# Sheet_1_2024-03-04.net
KiCad netlist of a schematic drawn in Altium Designer
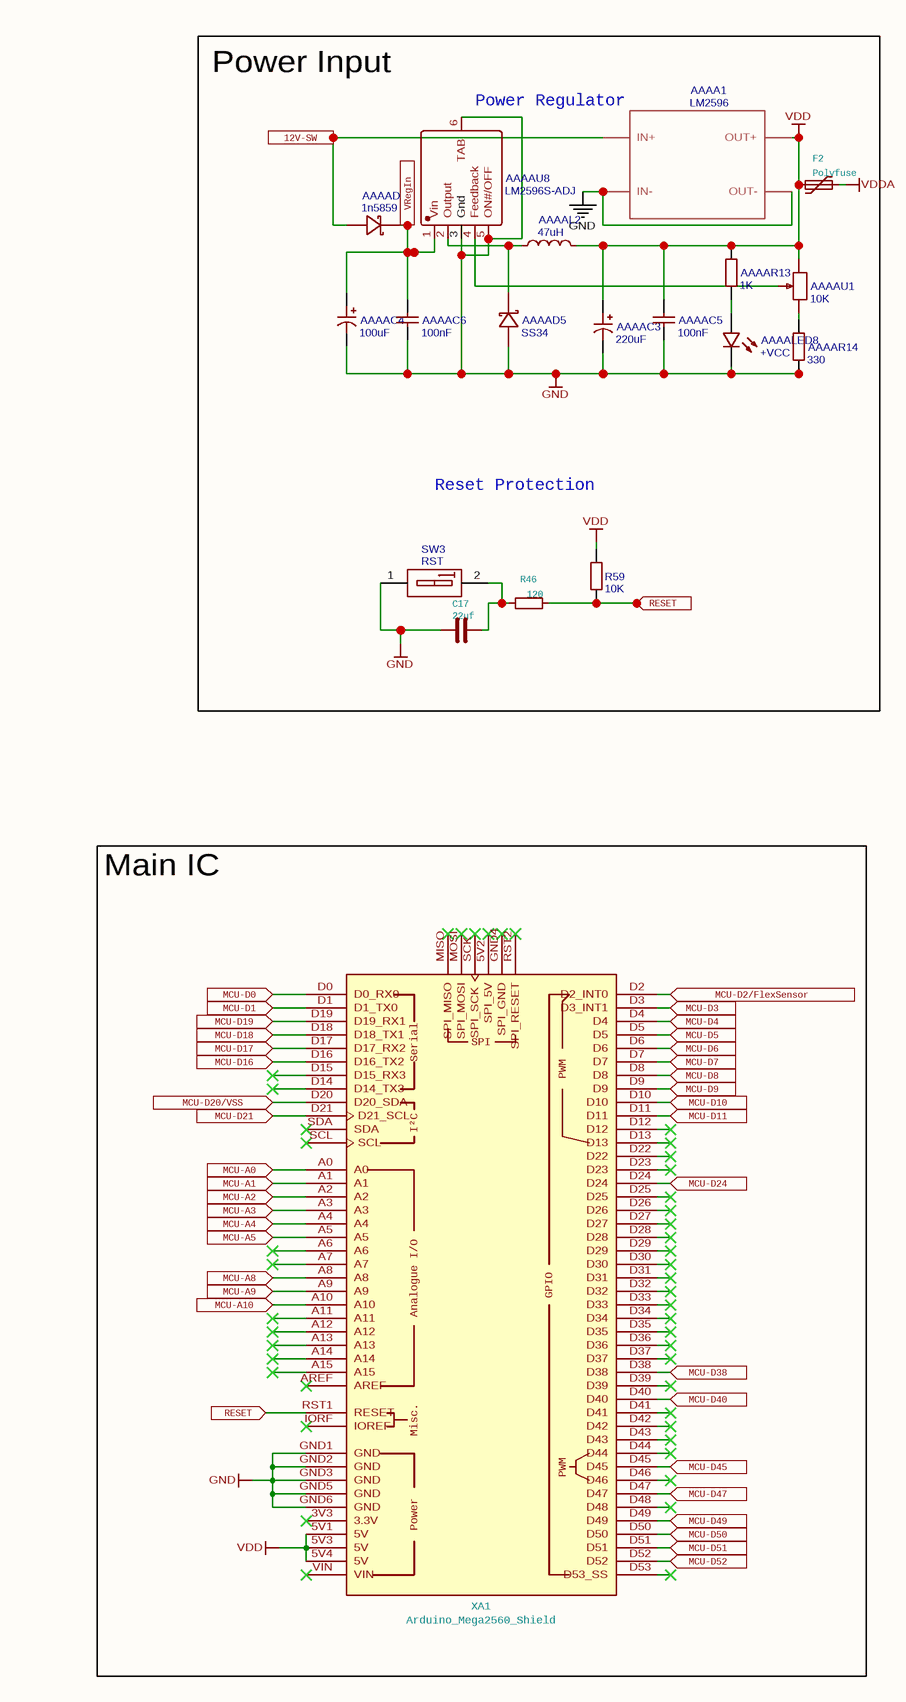
[diagram p0: Sheet_1_2024-03-04.schdoc, top left]
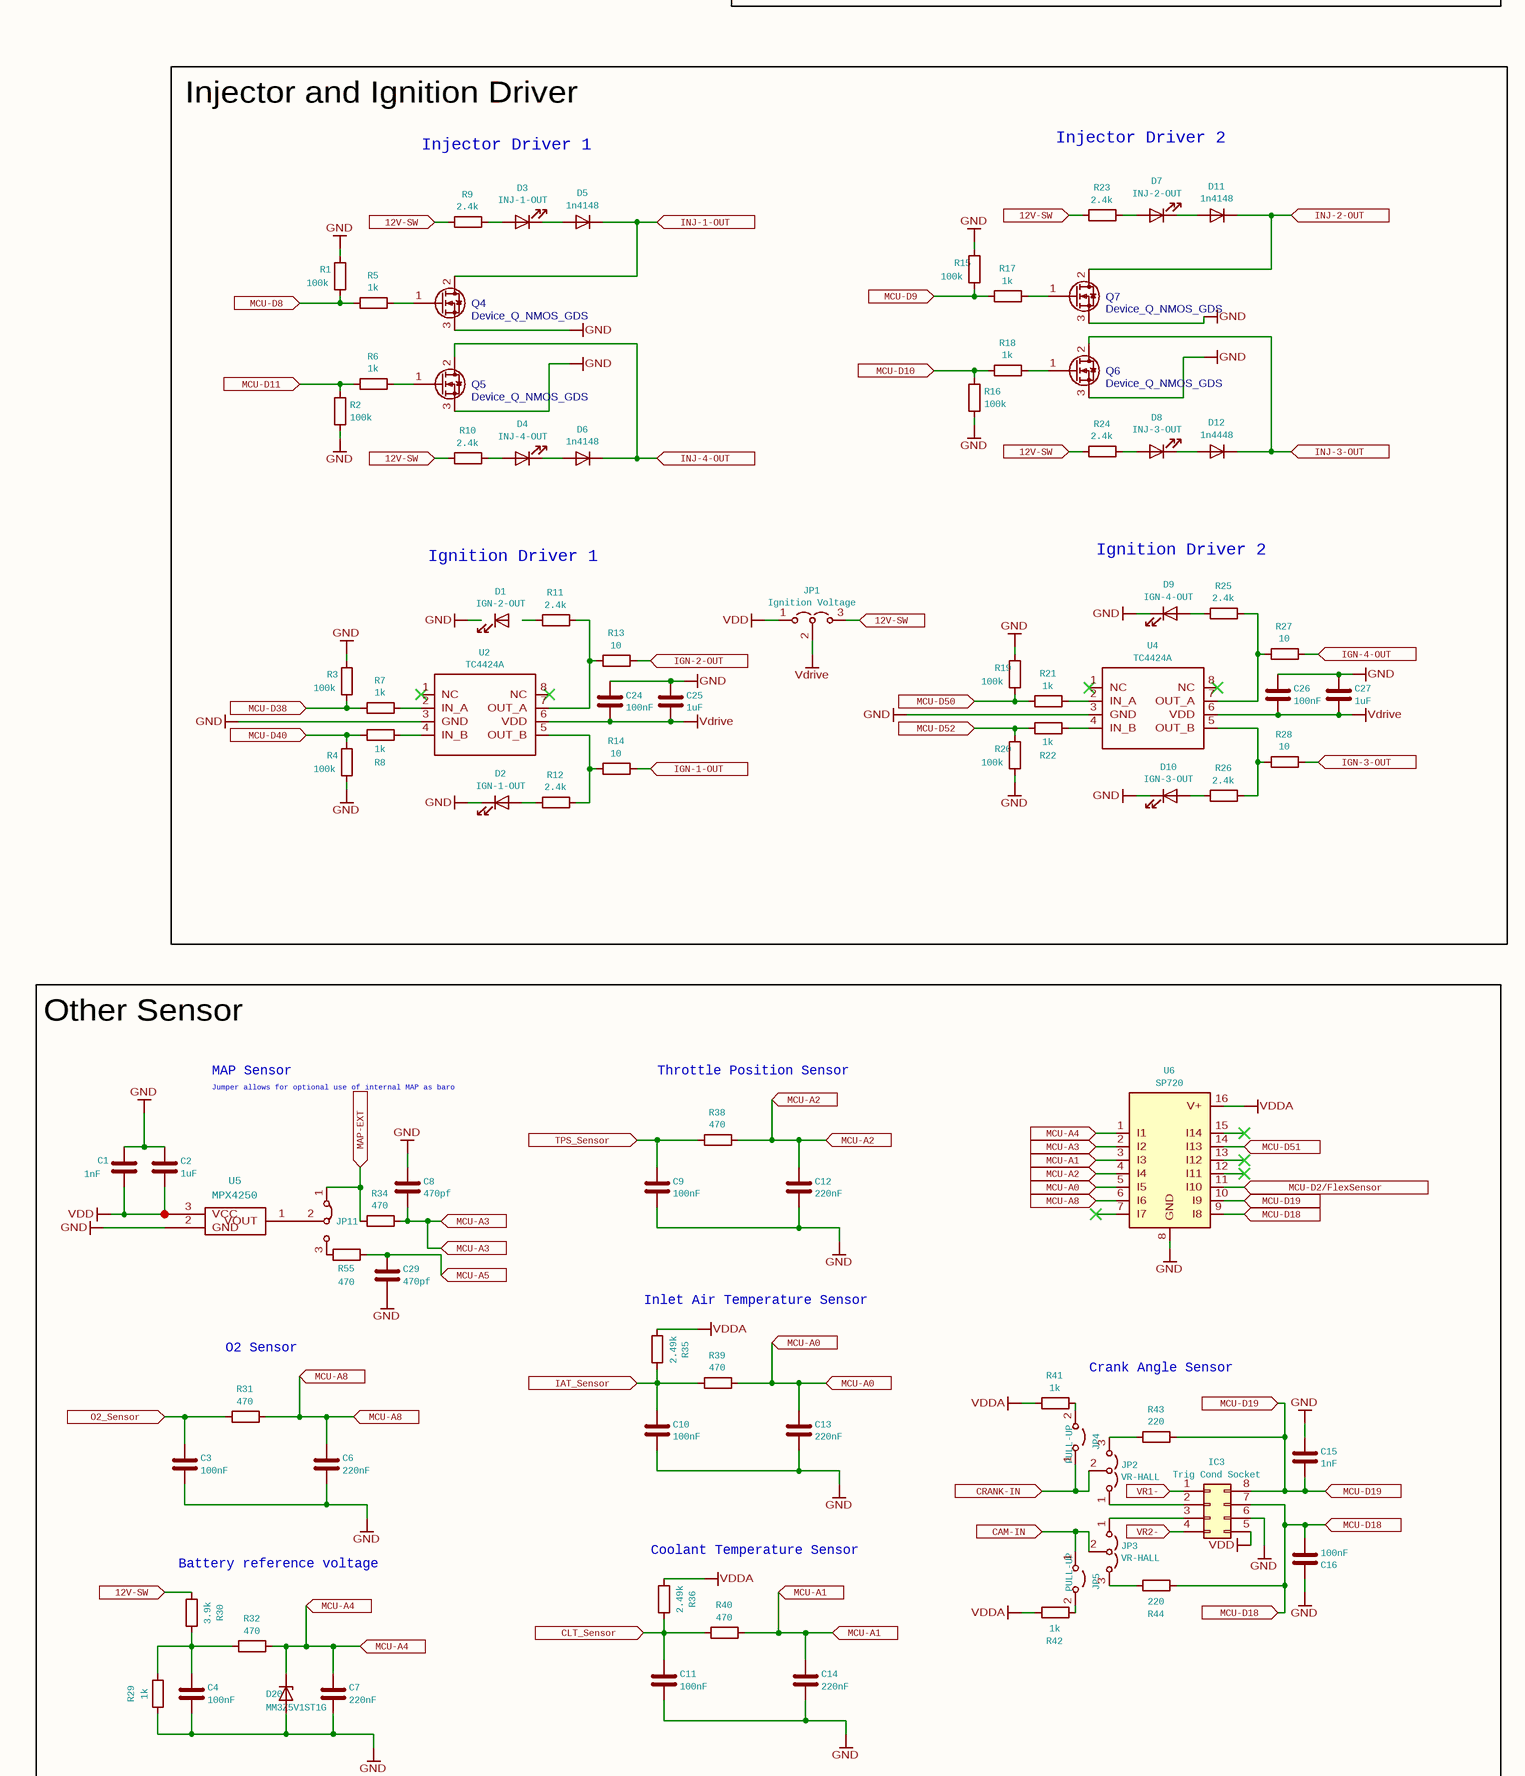
[diagram p1: Sheet_1_2024-03-04.schdoc, centre left]
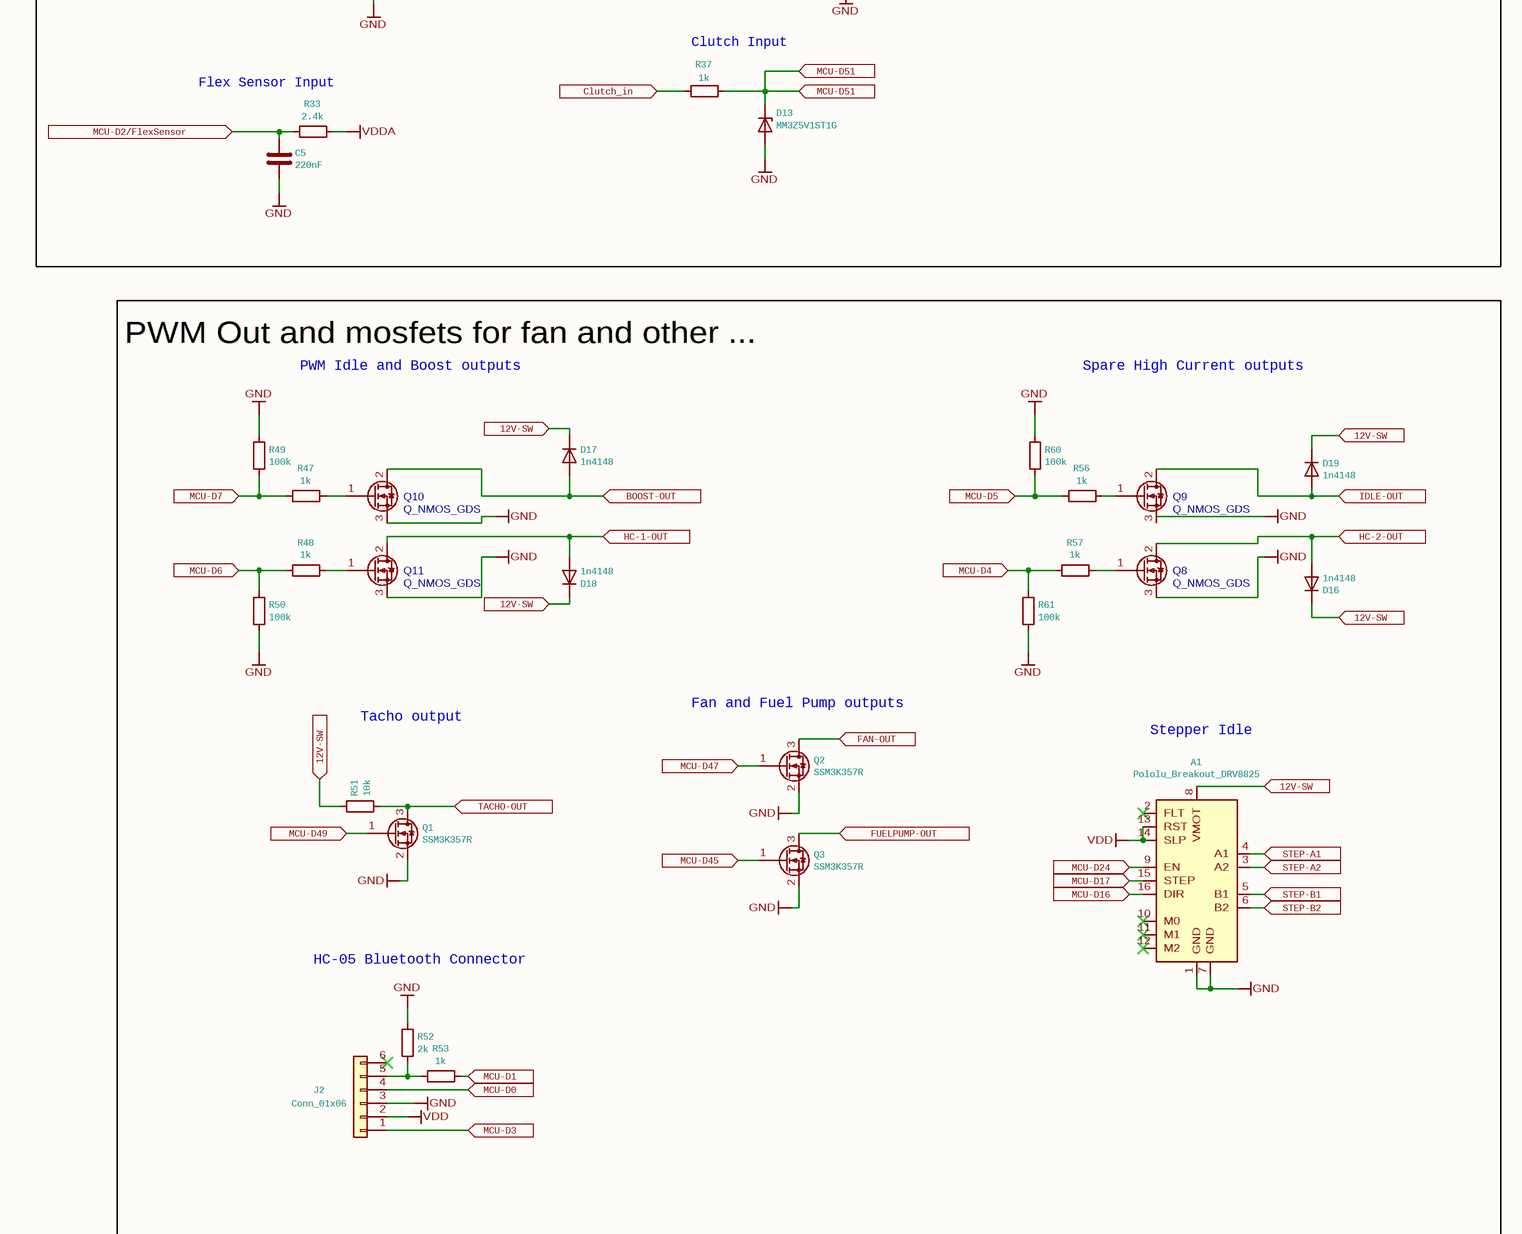
[diagram p2: Sheet_1_2024-03-04.schdoc, bottom left]
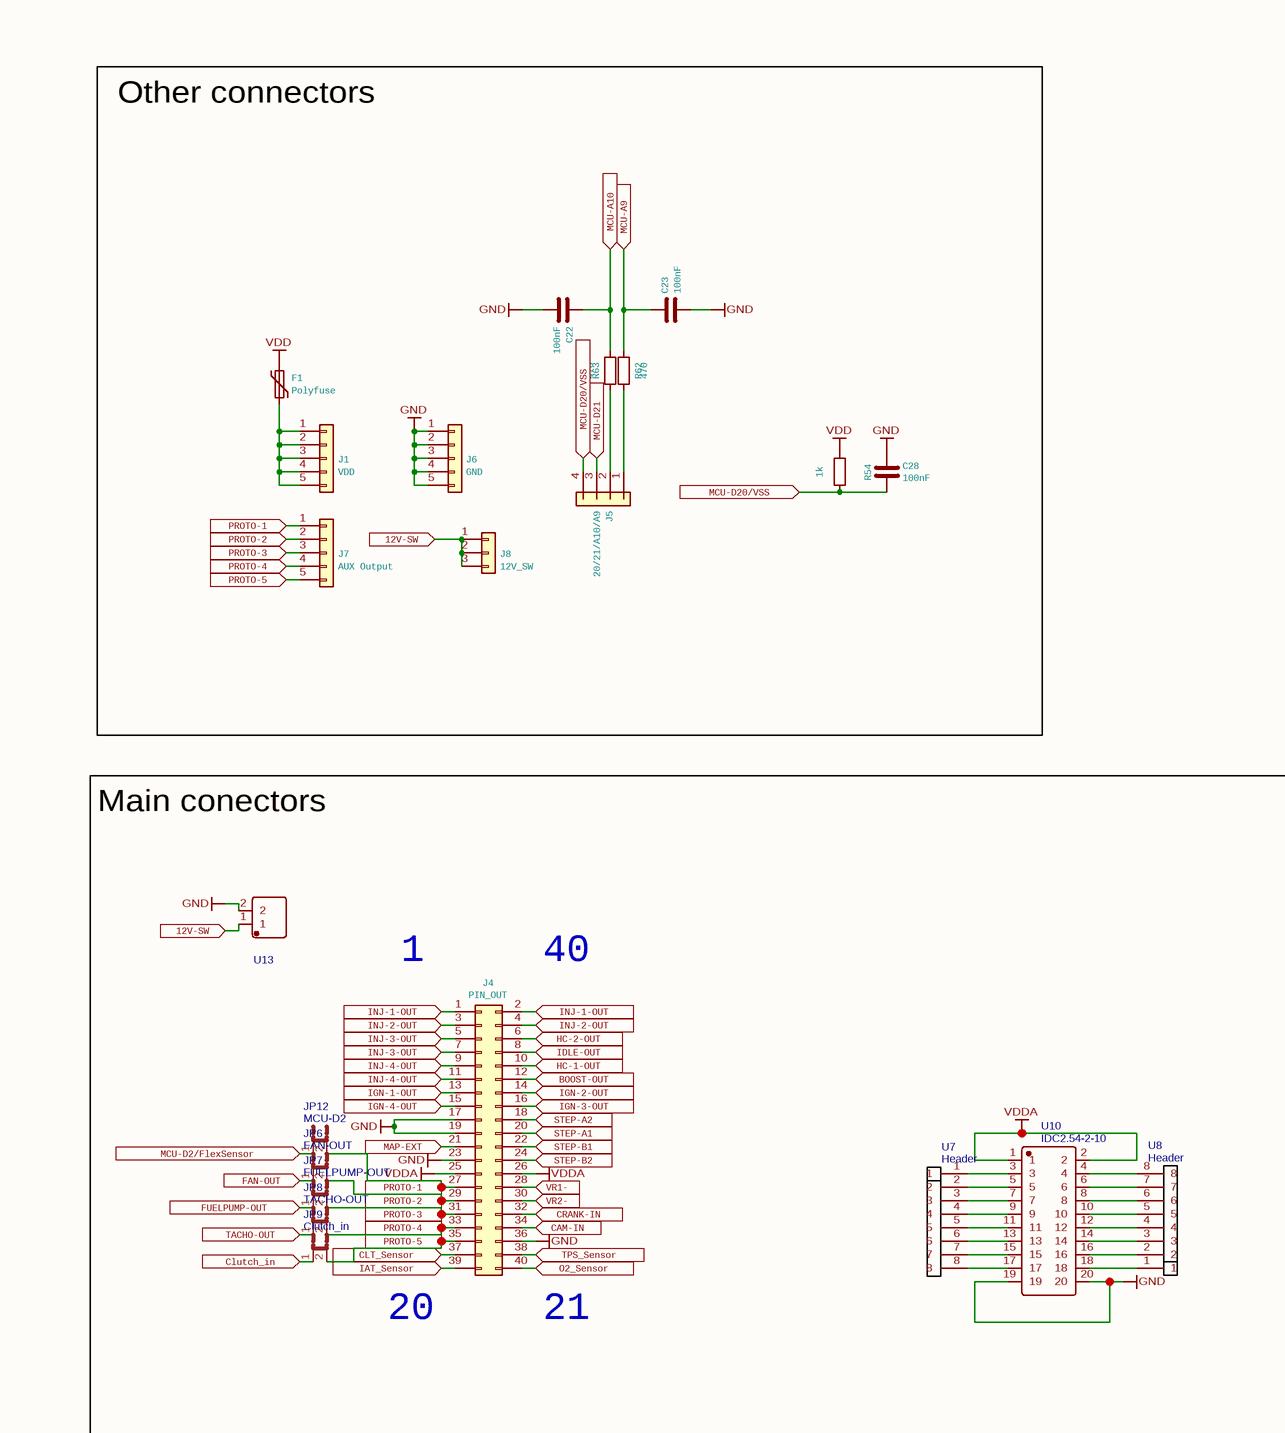
[diagram p3: Sheet_1_2024-03-04.schdoc, bottom right]

(export (version "E")
  (design (tool "Eeschema 10.0.6"))
  (components
    (comp (ref "A1")
      (value "Pololu_Breakout_DRV8825")
      (libsource (lib "altium-import") (part "root_0_Pololu_Breakout_DRV8825_"))
    )
    (comp (ref "AAAA1")
      (value "LM2596")
      (fields (field (name "CONTRIBUTOR") "Zufar Aditama"))
      (libsource (lib "altium-import") (part "root_0_LM2596_"))
    )
    (comp (ref "AAAAC3")
      (value "220uF")
      (fields
        (field (name "MANUFACTURER") "SAMYOUNG(韩国三莹)")
        (field (name "MANUFACTURER PART") "MVK16V100UF6.3*6")
        (field (name "CONTRIBUTOR") "amir slz")
      )
      (libsource (lib "altium-import") (part "root_3_220uF_"))
    )
    (comp (ref "AAAAC4")
      (value "100uF")
      (fields
        (field (name "MANUFACTURER") "SAMYOUNG(韩国三莹)")
        (field (name "MANUFACTURER PART") "MVK16V100UF6.3*6")
        (field (name "CONTRIBUTOR") "amir slz")
      )
      (libsource (lib "altium-import") (part "root_3_100uF_"))
    )
    (comp (ref "AAAAC5")
      (value "100nF")
      (fields
        (field (name "MANUFACTURER") "WTC")
        (field (name "MANUFACTURER PART") "0805F104Z500")
        (field (name "CONTRIBUTOR") "LCSC")
      )
      (libsource (lib "altium-import") (part "root_1_100nF_"))
    )
    (comp (ref "AAAAC6")
      (value "100nF")
      (fields
        (field (name "MANUFACTURER") "WTC")
        (field (name "MANUFACTURER PART") "0805F104Z500")
        (field (name "CONTRIBUTOR") "LCSC")
      )
      (libsource (lib "altium-import") (part "root_1_100nF_"))
    )
    (comp (ref "AAAAD1")
      (value "1n5859")
      (fields (field (name "MANUFACTURER PART") "SS34-55℃~+125℃") (field (name "CONTRIBUTOR") "lcsc"))
      (libsource (lib "altium-import") (part "root_2_1n5859_"))
    )
    (comp (ref "AAAAD5")
      (value "SS34")
      (fields (field (name "MANUFACTURER PART") "SS34-55℃~+125℃") (field (name "CONTRIBUTOR") "lcsc"))
      (libsource (lib "altium-import") (part "root_3_SS34_"))
    )
    (comp (ref "AAAAL2")
      (value "47uH")
      (fields
        (field (name "MANUFACTURER") "SHOU HAN(首韩)")
        (field (name "MANUFACTURER PART") "CYH127-47UH")
        (field (name "CONTRIBUTOR") "lcsc")
      )
      (libsource (lib "altium-import") (part "root_0_47uH_"))
    )
    (comp (ref "AAAALED8")
      (value "+VCC")
      (fields
        (field (name "MANUFACTURER") "Everlight Elec")
        (field (name "MANUFACTURER PART") "17-215/G6C-BM1N2L/3T")
        (field (name "CONTRIBUTOR") "LCSC")
      )
      (libsource (lib "altium-import") (part "root_3_+VCC_"))
    )
    (comp (ref "AAAAR13")
      (value "1K")
      (fields (field (name "MANUFACTURER PART") "CR0805-JW-393ELF") (field (name "CONTRIBUTOR") "lcsc"))
      (libsource (lib "altium-import") (part "root_1_1K_"))
    )
    (comp (ref "AAAAR14")
      (value "330")
      (fields (field (name "MANUFACTURER PART") "CR0805-JW-393ELF") (field (name "CONTRIBUTOR") "lcsc"))
      (libsource (lib "altium-import") (part "root_1_330_"))
    )
    (comp (ref "AAAAU1")
      (value "10K")
      (fields (field (name "MANUFACTURER PART") "SMD33-10K") (field (name "CONTRIBUTOR") "LCSC"))
      (libsource (lib "altium-import") (part "root_1_10K_"))
    )
    (comp (ref "AAAAU8")
      (value "LM2596S-ADJ")
      (fields
        (field (name "MANUFACTURER") "UMW(Youtai Semiconductor Co., Ltd.)")
        (field (name "CONTRIBUTOR") "LCSC")
      )
      (libsource (lib "altium-import") (part "root_1_LM2596S-ADJ_"))
    )
    (comp (ref "C1")
      (value "1nF")
      (fields
        (field (name "DIGIKEY PART NUMBER") "311-1136-1-ND")
        (field (name "MANUFACTURER_PART_NUMBER") "CC0805KRX7R9BB103")
      )
      (libsource (lib "altium-import") (part "root_0_1nF_"))
    )
    (comp (ref "C2")
      (value "1uF")
      (fields
        (field (name "DIGIKEY PART NUMBER") "311-1365-1-ND")
        (field (name "MANUFACTURER_PART_NUMBER") "CC0805KKX7R7BB105")
      )
      (libsource (lib "altium-import") (part "root_0_1uF_"))
    )
    (comp (ref "C3")
      (value "100nF")
      (fields
        (field (name "DIGIKEY PART NUMBER") "311-1140-1-ND")
        (field (name "MANUFACTURER_PART_NUMBER") "CC0805KRX7R9BB104")
      )
      (libsource (lib "altium-import") (part "root_0_100nF_"))
    )
    (comp (ref "C4")
      (value "100nF")
      (fields
        (field (name "DIGIKEY PART NUMBER") "311-1140-1-ND")
        (field (name "MANUFACTURER_PART_NUMBER") "CC0805KRX7R9BB104")
      )
      (libsource (lib "altium-import") (part "root_0_100nF_"))
    )
    (comp (ref "C5")
      (value "220nF")
      (fields
        (field (name "DIGIKEY PART NUMBER") "1276-1284-1-ND")
        (field (name "MANUFACTURER_PART_NUMBER") "CL21B224KOCNNNC")
      )
      (libsource (lib "altium-import") (part "root_0_220nF_"))
    )
    (comp (ref "C6")
      (value "220nF")
      (fields
        (field (name "DIGIKEY PART NUMBER") "1276-1284-1-ND")
        (field (name "MANUFACTURER_PART_NUMBER") "CL21B224KOCNNNC")
      )
      (libsource (lib "altium-import") (part "root_0_220nF_"))
    )
    (comp (ref "C7")
      (value "220nF")
      (fields
        (field (name "DIGIKEY PART NUMBER") "1276-1284-1-ND")
        (field (name "MANUFACTURER_PART_NUMBER") "CL21B224KOCNNNC")
      )
      (libsource (lib "altium-import") (part "root_0_220nF_"))
    )
    (comp (ref "C8")
      (value "470pf")
      (fields
        (field (name "DIGIKEY PART NUMBER") "311-1124-1-ND")
        (field (name "MANUFACTURER_PART_NUMBER") "CC0805KRX7R9BB471")
      )
      (libsource (lib "altium-import") (part "root_0_470pf_"))
    )
    (comp (ref "C9")
      (value "100nF")
      (fields
        (field (name "DIGIKEY PART NUMBER") "311-1140-1-ND")
        (field (name "MANUFACTURER_PART_NUMBER") "CC0805KRX7R9BB104")
      )
      (libsource (lib "altium-import") (part "root_0_100nF_"))
    )
    (comp (ref "C10")
      (value "100nF")
      (fields
        (field (name "DIGIKEY PART NUMBER") "311-1140-1-ND")
        (field (name "MANUFACTURER_PART_NUMBER") "CC0805KRX7R9BB104")
      )
      (libsource (lib "altium-import") (part "root_0_100nF_"))
    )
    (comp (ref "C11")
      (value "100nF")
      (fields
        (field (name "DIGIKEY PART NUMBER") "311-1140-1-ND")
        (field (name "MANUFACTURER_PART_NUMBER") "CC0805KRX7R9BB104")
      )
      (libsource (lib "altium-import") (part "root_0_100nF_"))
    )
    (comp (ref "C12")
      (value "220nF")
      (fields
        (field (name "DIGIKEY PART NUMBER") "1276-1284-1-ND")
        (field (name "MANUFACTURER_PART_NUMBER") "CL21B224KOCNNNC")
      )
      (libsource (lib "altium-import") (part "root_0_220nF_"))
    )
    (comp (ref "C13")
      (value "220nF")
      (fields
        (field (name "DIGIKEY PART NUMBER") "1276-1284-1-ND")
        (field (name "MANUFACTURER_PART_NUMBER") "CL21B224KOCNNNC")
      )
      (libsource (lib "altium-import") (part "root_0_220nF_"))
    )
    (comp (ref "C14")
      (value "220nF")
      (fields
        (field (name "DIGIKEY PART NUMBER") "1276-1284-1-ND")
        (field (name "MANUFACTURER_PART_NUMBER") "CL21B224KOCNNNC")
      )
      (libsource (lib "altium-import") (part "root_0_220nF_"))
    )
    (comp (ref "C15")
      (value "1nF")
      (fields
        (field (name "DIGIKEY PART NUMBER") "311-1136-1-ND")
        (field (name "MANUFACTURER_PART_NUMBER") "CC0805KRX7R9BB103")
      )
      (libsource (lib "altium-import") (part "root_0_1nF_"))
    )
    (comp (ref "C16")
      (value "100nF")
      (fields
        (field (name "DIGIKEY PART NUMBER") "311-1140-1-ND")
        (field (name "MANUFACTURER_PART_NUMBER") "CC0805KRX7R9BB104")
      )
      (libsource (lib "") (part "root_0_100nF__3"))
    )
    (comp (ref "C17")
      (value "22uf")
      (fields
        (field (name "DIGIKEY PART NUMBER") "311-1140-1-ND")
        (field (name "MANUFACTURER_PART_NUMBER") "CC0805KRX7R9BB104")
      )
      (libsource (lib "altium-import") (part "root_1_22uf_"))
    )
    (comp (ref "C22")
      (value "100nF")
      (fields
        (field (name "DIGIKEY PART NUMBER") "311-1140-1-ND")
        (field (name "MANUFACTURER_PART_NUMBER") "CC0805KRX7R9BB104")
      )
      (libsource (lib "") (part "root_0_100nF__1"))
    )
    (comp (ref "C23")
      (value "100nF")
      (fields
        (field (name "DIGIKEY PART NUMBER") "311-1140-1-ND")
        (field (name "MANUFACTURER_PART_NUMBER") "CC0805KRX7R9BB104")
      )
      (libsource (lib "") (part "root_0_100nF__2"))
    )
    (comp (ref "C24")
      (value "100nF")
      (fields
        (field (name "DIGIKEY PART NUMBER") "311-1140-1-ND")
        (field (name "MANUFACTURER_PART_NUMBER") "CC0805KRX7R9BB104")
      )
      (libsource (lib "altium-import") (part "root_0_100nF_"))
    )
    (comp (ref "C25")
      (value "1uF")
      (fields
        (field (name "DIGIKEY PART NUMBER") "311-1365-1-ND")
        (field (name "MANUFACTURER_PART_NUMBER") "CC0805KKX7R7BB105")
      )
      (libsource (lib "altium-import") (part "root_0_1uF_"))
    )
    (comp (ref "C26")
      (value "100nF")
      (fields
        (field (name "DIGIKEY PART NUMBER") "311-1140-1-ND")
        (field (name "MANUFACTURER_PART_NUMBER") "CC0805KRX7R9BB104")
      )
      (libsource (lib "altium-import") (part "root_0_100nF_"))
    )
    (comp (ref "C27")
      (value "1uF")
      (fields
        (field (name "DIGIKEY PART NUMBER") "311-1365-1-ND")
        (field (name "MANUFACTURER_PART_NUMBER") "CC0805KKX7R7BB105")
      )
      (libsource (lib "altium-import") (part "root_0_1uF_"))
    )
    (comp (ref "C28")
      (value "100nF")
      (fields
        (field (name "DIGIKEY PART NUMBER") "311-1140-1-ND")
        (field (name "MANUFACTURER_PART_NUMBER") "CC0805KRX7R9BB104")
      )
      (libsource (lib "altium-import") (part "root_0_100nF_"))
    )
    (comp (ref "C29")
      (value "470pf")
      (fields
        (field (name "DIGIKEY PART NUMBER") "311-1124-1-ND")
        (field (name "MANUFACTURER_PART_NUMBER") "CC0805KRX7R9BB471")
      )
      (libsource (lib "altium-import") (part "root_0_470pf_"))
    )
    (comp (ref "D1")
      (value "IGN-2-OUT")
      (fields
        (field (name "DIGIKEY PART NUMBER") "475-1415-1-ND")
        (field (name "MANUFACTURER_PART_NUMBER") "LH R974-LP-1")
      )
      (libsource (lib "altium-import") (part "root_0_IGN-2-OUT_"))
    )
    (comp (ref "D2")
      (value "IGN-1-OUT")
      (fields
        (field (name "DIGIKEY PART NUMBER") "475-1415-1-ND")
        (field (name "MANUFACTURER_PART_NUMBER") "LH R974-LP-1")
      )
      (libsource (lib "altium-import") (part "root_0_IGN-1-OUT_"))
    )
    (comp (ref "D3")
      (value "INJ-1-OUT")
      (fields
        (field (name "DIGIKEY PART NUMBER") "475-1415-1-ND")
        (field (name "MANUFACTURER_PART_NUMBER") "LH R974-LP-1")
      )
      (libsource (lib "altium-import") (part "root_0_INJ-1-OUT_"))
    )
    (comp (ref "D4")
      (value "INJ-4-OUT")
      (fields
        (field (name "DIGIKEY PART NUMBER") "475-1415-1-ND")
        (field (name "MANUFACTURER_PART_NUMBER") "LH R974-LP-1")
      )
      (libsource (lib "altium-import") (part "root_0_INJ-4-OUT_"))
    )
    (comp (ref "D5")
      (value "1n4148")
      (fields
        (field (name "DIGIKEY PART NUMBER") "1N4448WXTPMSCT-ND")
        (field (name "MANUFACTURER_PART_NUMBER") "1N4448WX-TP")
      )
      (libsource (lib "altium-import") (part "root_0_1n4148_"))
    )
    (comp (ref "D6")
      (value "1n4148")
      (fields
        (field (name "DIGIKEY PART NUMBER") "1N4448WXTPMSCT-ND")
        (field (name "MANUFACTURER_PART_NUMBER") "1N4448WX-TP")
      )
      (libsource (lib "altium-import") (part "root_0_1n4148_"))
    )
    (comp (ref "D7")
      (value "INJ-2-OUT")
      (fields
        (field (name "DIGIKEY PART NUMBER") "475-1415-1-ND")
        (field (name "MANUFACTURER_PART_NUMBER") "LH R974-LP-1")
      )
      (libsource (lib "altium-import") (part "root_0_INJ-2-OUT_"))
    )
    (comp (ref "D8")
      (value "INJ-3-OUT")
      (fields
        (field (name "DIGIKEY PART NUMBER") "475-1415-1-ND")
        (field (name "MANUFACTURER_PART_NUMBER") "LH R974-LP-1")
      )
      (libsource (lib "altium-import") (part "root_0_INJ-3-OUT_"))
    )
    (comp (ref "D9")
      (value "IGN-4-OUT")
      (fields
        (field (name "DIGIKEY PART NUMBER") "475-1415-1-ND")
        (field (name "MANUFACTURER_PART_NUMBER") "LH R974-LP-1")
      )
      (libsource (lib "altium-import") (part "root_0_IGN-4-OUT_"))
    )
    (comp (ref "D10")
      (value "IGN-3-OUT")
      (fields
        (field (name "DIGIKEY PART NUMBER") "475-1415-1-ND")
        (field (name "MANUFACTURER_PART_NUMBER") "LH R974-LP-1")
      )
      (libsource (lib "altium-import") (part "root_0_IGN-3-OUT_"))
    )
    (comp (ref "D11")
      (value "1n4148")
      (fields
        (field (name "DIGIKEY PART NUMBER") "1N4448WXTPMSCT-ND")
        (field (name "MANUFACTURER_PART_NUMBER") "1N4448WX-TP")
      )
      (libsource (lib "altium-import") (part "root_0_1n4148_"))
    )
    (comp (ref "D12")
      (value "1n4448")
      (fields
        (field (name "DIGIKEY PART NUMBER") "1N4448WXTPMSCT-ND")
        (field (name "MANUFACTURER_PART_NUMBER") "1N4448WX-TP")
      )
      (libsource (lib "altium-import") (part "root_0_1n4448_"))
    )
    (comp (ref "D13")
      (value "MM3Z5V1ST1G")
      (fields (field (name "DIGIKEY PART NUMBER") "MM3Z5V1ST1GOSCT-ND"))
      (libsource (lib "altium-import") (part "root_0_MM3Z5V1ST1G_"))
    )
    (comp (ref "D16")
      (value "1n4148")
      (fields
        (field (name "DIGIKEY PART NUMBER") "S110FACT-ND")
        (field (name "MANUFACTURER_PART_NUMBER") "S110FA")
      )
      (libsource (lib "") (part "root_0_1n4148__1"))
    )
    (comp (ref "D17")
      (value "1n4148")
      (fields
        (field (name "DIGIKEY PART NUMBER") "S110FACT-ND")
        (field (name "MANUFACTURER_PART_NUMBER") "S110FA")
      )
      (libsource (lib "") (part "root_0_1n4148__2"))
    )
    (comp (ref "D18")
      (value "1n4148")
      (fields
        (field (name "DIGIKEY PART NUMBER") "S110FACT-ND")
        (field (name "MANUFACTURER_PART_NUMBER") "S110FA")
      )
      (libsource (lib "") (part "root_0_1n4148__1"))
    )
    (comp (ref "D19")
      (value "1n4148")
      (fields
        (field (name "DIGIKEY PART NUMBER") "S110FACT-ND")
        (field (name "MANUFACTURER_PART_NUMBER") "S110FA")
      )
      (libsource (lib "") (part "root_0_1n4148__2"))
    )
    (comp (ref "D20")
      (value "MM3Z5V1ST1G")
      (fields (field (name "DIGIKEY PART NUMBER") "MM3Z5V1ST1GOSCT-ND"))
      (libsource (lib "altium-import") (part "root_0_MM3Z5V1ST1G_"))
    )
    (comp (ref "F1")
      (value "Polyfuse")
      (fields
        (field (name "DIGIKEY PART NUMBER") "507-1361-1-ND")
        (field (name "MANUFACTURER_PART_NUMBER") "0ZCC0050FF2C")
      )
      (libsource (lib "altium-import") (part "root_0_Polyfuse_"))
    )
    (comp (ref "F2")
      (value "Polyfuse")
      (fields
        (field (name "DIGIKEY PART NUMBER") "507-1361-1-ND")
        (field (name "MANUFACTURER_PART_NUMBER") "0ZCC0050FF2C")
      )
      (libsource (lib "altium-import") (part "root_1_Polyfuse_"))
    )
    (comp (ref "IC3")
      (value "Trig Cond Socket")
      (libsource (lib "altium-import") (part "root_0_Trig Cond Socket_"))
    )
    (comp (ref "J1") (value "VDD") (libsource (lib "altium-import") (part "root_0_VDD_")))
    (comp (ref "J2") (value "Conn_01x06") (libsource (lib "altium-import") (part "root_0_Conn_01x06_")))
    (comp (ref "J4") (value "PIN_OUT") (libsource (lib "altium-import") (part "root_0_PIN_OUT_")))
    (comp (ref "J5") (value "20/21/A10/A9") (libsource (lib "altium-import") (part "root_0_20/21/A10/A9_")))
    (comp (ref "J6") (value "GND") (libsource (lib "altium-import") (part "root_0_GND_")))
    (comp (ref "J7") (value "AUX Output") (libsource (lib "altium-import") (part "root_0_AUX Output_")))
    (comp (ref "J8") (value "12V_SW") (libsource (lib "altium-import") (part "root_0_12V_SW_")))
    (comp (ref "JP1")
      (value "Ignition Voltage")
      (fields
        (field (name "DIGIKEY PART NUMBER") "952-2263-ND")
        (field (name "MANUFACTURER_PART_NUMBER") "M20-9990345")
      )
      (libsource (lib "altium-import") (part "root_0_Ignition Voltage_"))
    )
    (comp (ref "JP2")
      (value "VR-HALL")
      (fields
        (field (name "DIGIKEY PART NUMBER") "952-2263-ND")
        (field (name "MANUFACTURER_PART_NUMBER") "M20-9990345")
      )
      (libsource (lib "") (part "root_0_VR-HALL__1"))
    )
    (comp (ref "JP3")
      (value "VR-HALL")
      (fields
        (field (name "DIGIKEY PART NUMBER") "952-2263-ND")
        (field (name "MANUFACTURER_PART_NUMBER") "M20-9990345")
      )
      (libsource (lib "altium-import") (part "root_0_VR-HALL_"))
    )
    (comp (ref "JP4")
      (value "PULL-UP")
      (fields
        (field (name "DIGIKEY PART NUMBER") "952-2261-ND")
        (field (name "MANUFACTURER_PART_NUMBER") "M20-9990245")
      )
      (libsource (lib "altium-import") (part "root_0_PULL-UP_"))
    )
    (comp (ref "JP5")
      (value "PULL-UP")
      (fields
        (field (name "DIGIKEY PART NUMBER") "952-2261-ND")
        (field (name "MANUFACTURER_PART_NUMBER") "M20-9990245")
      )
      (libsource (lib "") (part "root_0_PULL-UP__1"))
    )
    (comp (ref "JP6")
      (value "FAN-OUT")
      (description "Jumper 2 Pin")
      (fields (field (name "CONTRIBUTOR") "amir slz"))
      (libsource (lib "altium-import") (part "root_0_FAN-OUT_"))
    )
    (comp (ref "JP7")
      (value "FUELPUMP-OUT")
      (description "Jumper 2 Pin")
      (fields (field (name "CONTRIBUTOR") "amir slz"))
      (libsource (lib "altium-import") (part "root_0_FUELPUMP-OUT_"))
    )
    (comp (ref "JP8")
      (value "TACHO-OUT")
      (description "Jumper 2 Pin")
      (fields (field (name "CONTRIBUTOR") "amir slz"))
      (libsource (lib "altium-import") (part "root_0_TACHO-OUT_"))
    )
    (comp (ref "JP9")
      (value "Clutch_in")
      (description "Jumper 2 Pin")
      (fields (field (name "CONTRIBUTOR") "amir slz"))
      (libsource (lib "altium-import") (part "root_0_Clutch_in_"))
    )
    (comp (ref "JP11") (value "Jumper_MPX") (libsource (lib "altium-import") (part "root_0_Jumper_MPX_")))
    (comp (ref "JP12")
      (value "MCU-D2")
      (description "Jumper 2 Pin")
      (fields (field (name "CONTRIBUTOR") "amir slz"))
      (libsource (lib "altium-import") (part "root_0_MCU-D2_"))
    )
    (comp (ref "Q1")
      (value "SSM3K357R")
      (fields (field (name "DIGIKEY PART NUMBER") "SSM3K357RLFCT-ND"))
      (libsource (lib "altium-import") (part "root_0_SSM3K357R_"))
    )
    (comp (ref "Q2")
      (value "SSM3K357R")
      (fields (field (name "DIGIKEY PART NUMBER") "SSM3K357RLFCT-ND"))
      (libsource (lib "altium-import") (part "root_0_SSM3K357R_"))
    )
    (comp (ref "Q3")
      (value "SSM3K357R")
      (fields (field (name "DIGIKEY PART NUMBER") "SSM3K357RLFCT-ND"))
      (libsource (lib "altium-import") (part "root_0_SSM3K357R_"))
    )
    (comp (ref "Q4")
      (value "Device_Q_NMOS_GDS")
      (fields (field (name "CONTRIBUTOR") "amir slz"))
      (libsource (lib "altium-import") (part "root_0_Device_Q_NMOS_GDS_"))
    )
    (comp (ref "Q5")
      (value "Device_Q_NMOS_GDS")
      (fields (field (name "CONTRIBUTOR") "amir slz"))
      (libsource (lib "altium-import") (part "root_0_Device_Q_NMOS_GDS_"))
    )
    (comp (ref "Q6")
      (value "Device_Q_NMOS_GDS")
      (fields (field (name "CONTRIBUTOR") "amir slz"))
      (libsource (lib "altium-import") (part "root_0_Device_Q_NMOS_GDS_"))
    )
    (comp (ref "Q7")
      (value "Device_Q_NMOS_GDS")
      (fields (field (name "CONTRIBUTOR") "amir slz"))
      (libsource (lib "altium-import") (part "root_0_Device_Q_NMOS_GDS_"))
    )
    (comp (ref "Q8")
      (value "Q_NMOS_GDS")
      (fields (field (name "CONTRIBUTOR") "amir slz"))
      (libsource (lib "altium-import") (part "root_0_Q_NMOS_GDS_"))
    )
    (comp (ref "Q9")
      (value "Q_NMOS_GDS")
      (fields (field (name "CONTRIBUTOR") "amir slz"))
      (libsource (lib "altium-import") (part "root_0_Q_NMOS_GDS_"))
    )
    (comp (ref "Q10")
      (value "Q_NMOS_GDS")
      (fields (field (name "CONTRIBUTOR") "amir slz"))
      (libsource (lib "altium-import") (part "root_0_Q_NMOS_GDS_"))
    )
    (comp (ref "Q11")
      (value "Q_NMOS_GDS")
      (fields (field (name "CONTRIBUTOR") "amir slz"))
      (libsource (lib "altium-import") (part "root_0_Q_NMOS_GDS_"))
    )
    (comp (ref "R1")
      (value "100k")
      (fields
        (field (name "DIGIKEY PART NUMBER") "311-100KCRCT-ND")
        (field (name "MANUFACTURER_PART_NUMBER") "RC0805FR-07100KL")
      )
      (libsource (lib "altium-import") (part "root_0_100k_"))
    )
    (comp (ref "R2")
      (value "100k")
      (fields
        (field (name "DIGIKEY PART NUMBER") "311-100KCRCT-ND")
        (field (name "MANUFACTURER_PART_NUMBER") "RC0805FR-07100KL")
      )
      (libsource (lib "altium-import") (part "root_0_100k_"))
    )
    (comp (ref "R3")
      (value "100k")
      (fields
        (field (name "DIGIKEY PART NUMBER") "311-100KCRCT-ND")
        (field (name "MANUFACTURER_PART_NUMBER") "RC0805FR-07100KL")
      )
      (libsource (lib "altium-import") (part "root_0_100k_"))
    )
    (comp (ref "R4")
      (value "100k")
      (fields
        (field (name "DIGIKEY PART NUMBER") "311-100KCRCT-ND")
        (field (name "MANUFACTURER_PART_NUMBER") "RC0805FR-07100KL")
      )
      (libsource (lib "altium-import") (part "root_0_100k_"))
    )
    (comp (ref "R5")
      (value "1k")
      (fields
        (field (name "DIGIKEY PART NUMBER") "311-1.00KCRCT-ND")
        (field (name "MANUFACTURER_PART_NUMBER") "RC0805FR-071KL")
      )
      (libsource (lib "altium-import") (part "root_0_1k_"))
    )
    (comp (ref "R6")
      (value "1k")
      (fields
        (field (name "DIGIKEY PART NUMBER") "311-1.00KCRCT-ND")
        (field (name "MANUFACTURER_PART_NUMBER") "RC0805FR-071KL")
      )
      (libsource (lib "altium-import") (part "root_0_1k_"))
    )
    (comp (ref "R7")
      (value "1k")
      (fields
        (field (name "DIGIKEY PART NUMBER") "311-1.00KCRCT-ND")
        (field (name "MANUFACTURER_PART_NUMBER") "RC0805FR-071KL")
      )
      (libsource (lib "altium-import") (part "root_0_1k_"))
    )
    (comp (ref "R8")
      (value "1k")
      (fields
        (field (name "DIGIKEY PART NUMBER") "311-1.00KCRCT-ND")
        (field (name "MANUFACTURER_PART_NUMBER") "RC0805FR-071KL")
      )
      (libsource (lib "altium-import") (part "root_0_1k_"))
    )
    (comp (ref "R9")
      (value "2.4k")
      (fields
        (field (name "DIGIKEY PART NUMBER") "311-2.40KCRCT-ND")
        (field (name "MANUFACTURER_PART_NUMBER") "RC0805FR-072K4L")
      )
      (libsource (lib "altium-import") (part "root_0_2.4k_"))
    )
    (comp (ref "R10")
      (value "2.4k")
      (fields
        (field (name "DIGIKEY PART NUMBER") "311-2.40KCRCT-ND")
        (field (name "MANUFACTURER_PART_NUMBER") "RC0805FR-072K4L")
      )
      (libsource (lib "altium-import") (part "root_0_2.4k_"))
    )
    (comp (ref "R11")
      (value "2.4k")
      (fields
        (field (name "DIGIKEY PART NUMBER") "311-2.40KCRCT-ND")
        (field (name "MANUFACTURER_PART_NUMBER") "RC0805FR-072K4L")
      )
      (libsource (lib "altium-import") (part "root_0_2.4k_"))
    )
    (comp (ref "R12")
      (value "2.4k")
      (fields
        (field (name "DIGIKEY PART NUMBER") "311-2.40KCRCT-ND")
        (field (name "MANUFACTURER_PART_NUMBER") "RC0805FR-072K4L")
      )
      (libsource (lib "altium-import") (part "root_0_2.4k_"))
    )
    (comp (ref "R13")
      (value "10")
      (fields
        (field (name "DIGIKEY PART NUMBER") "311-10.0FRCT-ND")
        (field (name "MANUFACTURER_PART_NUMBER") "RC1206FR-0710RL")
      )
      (libsource (lib "altium-import") (part "root_0_10_"))
    )
    (comp (ref "R14")
      (value "10")
      (fields
        (field (name "DIGIKEY PART NUMBER") "311-10.0FRCT-ND")
        (field (name "MANUFACTURER_PART_NUMBER") "RC1206FR-0710RL")
      )
      (libsource (lib "altium-import") (part "root_0_10_"))
    )
    (comp (ref "R15")
      (value "100k")
      (fields
        (field (name "DIGIKEY PART NUMBER") "311-100KCRCT-ND")
        (field (name "MANUFACTURER_PART_NUMBER") "RC0805FR-07100KL")
      )
      (libsource (lib "altium-import") (part "root_0_100k_"))
    )
    (comp (ref "R16")
      (value "100k")
      (fields
        (field (name "DIGIKEY PART NUMBER") "311-100KCRCT-ND")
        (field (name "MANUFACTURER_PART_NUMBER") "RC0805FR-07100KL")
      )
      (libsource (lib "altium-import") (part "root_0_100k_"))
    )
    (comp (ref "R17")
      (value "1k")
      (fields
        (field (name "DIGIKEY PART NUMBER") "311-1.00KCRCT-ND")
        (field (name "MANUFACTURER_PART_NUMBER") "RC0805FR-071KL")
      )
      (libsource (lib "altium-import") (part "root_0_1k_"))
    )
    (comp (ref "R18")
      (value "1k")
      (fields
        (field (name "DIGIKEY PART NUMBER") "311-1.00KCRCT-ND")
        (field (name "MANUFACTURER_PART_NUMBER") "RC0805FR-071KL")
      )
      (libsource (lib "altium-import") (part "root_0_1k_"))
    )
    (comp (ref "R19")
      (value "100k")
      (fields
        (field (name "DIGIKEY PART NUMBER") "311-100KCRCT-ND")
        (field (name "MANUFACTURER_PART_NUMBER") "RC0805FR-07100KL")
      )
      (libsource (lib "altium-import") (part "root_0_100k_"))
    )
    (comp (ref "R20")
      (value "100k")
      (fields
        (field (name "DIGIKEY PART NUMBER") "311-100KCRCT-ND")
        (field (name "MANUFACTURER_PART_NUMBER") "RC0805FR-07100KL")
      )
      (libsource (lib "altium-import") (part "root_0_100k_"))
    )
    (comp (ref "R21")
      (value "1k")
      (fields
        (field (name "DIGIKEY PART NUMBER") "311-1.00KCRCT-ND")
        (field (name "MANUFACTURER_PART_NUMBER") "RC0805FR-071KL")
      )
      (libsource (lib "altium-import") (part "root_0_1k_"))
    )
    (comp (ref "R22")
      (value "1k")
      (fields
        (field (name "DIGIKEY PART NUMBER") "311-1.00KCRCT-ND")
        (field (name "MANUFACTURER_PART_NUMBER") "RC0805FR-071KL")
      )
      (libsource (lib "altium-import") (part "root_0_1k_"))
    )
    (comp (ref "R23")
      (value "2.4k")
      (fields
        (field (name "DIGIKEY PART NUMBER") "311-2.40KCRCT-ND")
        (field (name "MANUFACTURER_PART_NUMBER") "RC0805FR-072K4L")
      )
      (libsource (lib "altium-import") (part "root_0_2.4k_"))
    )
    (comp (ref "R24")
      (value "2.4k")
      (fields
        (field (name "DIGIKEY PART NUMBER") "311-2.40KCRCT-ND")
        (field (name "MANUFACTURER_PART_NUMBER") "RC0805FR-072K4L")
      )
      (libsource (lib "altium-import") (part "root_0_2.4k_"))
    )
    (comp (ref "R25")
      (value "2.4k")
      (fields
        (field (name "DIGIKEY PART NUMBER") "311-2.40KCRCT-ND")
        (field (name "MANUFACTURER_PART_NUMBER") "RC0805FR-072K4L")
      )
      (libsource (lib "altium-import") (part "root_0_2.4k_"))
    )
    (comp (ref "R26")
      (value "2.4k")
      (fields
        (field (name "DIGIKEY PART NUMBER") "311-2.40KCRCT-ND")
        (field (name "MANUFACTURER_PART_NUMBER") "RC0805FR-072K4L")
      )
      (libsource (lib "altium-import") (part "root_0_2.4k_"))
    )
    (comp (ref "R27")
      (value "10")
      (fields
        (field (name "DIGIKEY PART NUMBER") "311-10.0FRCT-ND")
        (field (name "MANUFACTURER_PART_NUMBER") "RC1206FR-0710RL")
      )
      (libsource (lib "altium-import") (part "root_0_10_"))
    )
    (comp (ref "R28")
      (value "10")
      (fields
        (field (name "DIGIKEY PART NUMBER") "311-10.0FRCT-ND")
        (field (name "MANUFACTURER_PART_NUMBER") "RC1206FR-0710RL")
      )
      (libsource (lib "altium-import") (part "root_0_10_"))
    )
    (comp (ref "R29")
      (value "1k")
      (fields
        (field (name "DIGIKEY PART NUMBER") "311-1.00KCRCT-ND")
        (field (name "MANUFACTURER_PART_NUMBER") "RC0805FR-071KL")
      )
      (libsource (lib "") (part "root_0_1k__1"))
    )
    (comp (ref "R30")
      (value "3.9k")
      (fields
        (field (name "DIGIKEY PART NUMBER") "311-3.90KCRCT-ND")
        (field (name "MANUFACTURER_PART_NUMBER") "RC0805FR-073K9L")
      )
      (libsource (lib "altium-import") (part "root_0_3.9k_"))
    )
    (comp (ref "R31")
      (value "470")
      (fields
        (field (name "MANUFACTURER_PART_NUMBER") "ERJ-6ENF4700V")
        (field (name "DIGIKEY PART NUMBER") "P470CCT-ND")
      )
      (libsource (lib "") (part "root_0_470__2"))
    )
    (comp (ref "R32")
      (value "470")
      (fields
        (field (name "MANUFACTURER_PART_NUMBER") "ERJ-6ENF4700V")
        (field (name "DIGIKEY PART NUMBER") "P470CCT-ND")
      )
      (libsource (lib "") (part "root_0_470__2"))
    )
    (comp (ref "R33")
      (value "2.4k")
      (fields
        (field (name "DIGIKEY PART NUMBER") "311-2.40KCRCT-ND")
        (field (name "MANUFACTURER_PART_NUMBER") "RC0805FR-072K4L")
      )
      (libsource (lib "altium-import") (part "root_0_2.4k_"))
    )
    (comp (ref "R34")
      (value "470")
      (fields
        (field (name "MANUFACTURER_PART_NUMBER") "ERJ-6ENF4700V")
        (field (name "DIGIKEY PART NUMBER") "P470CCT-ND")
      )
      (libsource (lib "") (part "root_0_470__2"))
    )
    (comp (ref "R35")
      (value "2.49k")
      (fields
        (field (name "DIGIKEY PART NUMBER") "YAG1854CT-ND")
        (field (name "MANUFACTURER_PART_NUMBER") "RT0805BRD072K49L")
      )
      (libsource (lib "altium-import") (part "root_0_2.49k_"))
    )
    (comp (ref "R36")
      (value "2.49k")
      (fields
        (field (name "DIGIKEY PART NUMBER") "YAG1854CT-ND")
        (field (name "MANUFACTURER_PART_NUMBER") "RT0805BRD072K49L")
      )
      (libsource (lib "altium-import") (part "root_0_2.49k_"))
    )
    (comp (ref "R37")
      (value "1k")
      (fields
        (field (name "DIGIKEY PART NUMBER") "311-1.00KCRCT-ND")
        (field (name "MANUFACTURER_PART_NUMBER") "RC0805FR-071KL")
      )
      (libsource (lib "") (part "root_0_1k__2"))
    )
    (comp (ref "R38")
      (value "470")
      (fields
        (field (name "MANUFACTURER_PART_NUMBER") "ERJ-6ENF4700V")
        (field (name "DIGIKEY PART NUMBER") "P470CCT-ND")
      )
      (libsource (lib "") (part "root_0_470__2"))
    )
    (comp (ref "R39")
      (value "470")
      (fields
        (field (name "MANUFACTURER_PART_NUMBER") "ERJ-6ENF4700V")
        (field (name "DIGIKEY PART NUMBER") "P470CCT-ND")
      )
      (libsource (lib "") (part "root_0_470__2"))
    )
    (comp (ref "R40")
      (value "470")
      (fields
        (field (name "MANUFACTURER_PART_NUMBER") "ERJ-6ENF4700V")
        (field (name "DIGIKEY PART NUMBER") "P470CCT-ND")
      )
      (libsource (lib "") (part "root_0_470__2"))
    )
    (comp (ref "R41")
      (value "1k")
      (fields
        (field (name "DIGIKEY PART NUMBER") "311-1.00KCRCT-ND")
        (field (name "MANUFACTURER_PART_NUMBER") "RC0805FR-071KL")
      )
      (libsource (lib "altium-import") (part "root_0_1k_"))
    )
    (comp (ref "R42")
      (value "1k")
      (fields
        (field (name "DIGIKEY PART NUMBER") "311-1.00KCRCT-ND")
        (field (name "MANUFACTURER_PART_NUMBER") "RC0805FR-071KL")
      )
      (libsource (lib "altium-import") (part "root_0_1k_"))
    )
    (comp (ref "R43")
      (value "220")
      (fields
        (field (name "DIGIKEY PART NUMBER") "311-220CRCT-ND")
        (field (name "MANUFACTURER_PART_NUMBER") "RC0805FR-07220RL")
      )
      (libsource (lib "altium-import") (part "root_0_220_"))
    )
    (comp (ref "R44")
      (value "220")
      (fields
        (field (name "DIGIKEY PART NUMBER") "311-220CRCT-ND")
        (field (name "MANUFACTURER_PART_NUMBER") "RC0805FR-07220RL")
      )
      (libsource (lib "altium-import") (part "root_0_220_"))
    )
    (comp (ref "R46")
      (value "120")
      (fields
        (field (name "DIGIKEY PART NUMBER") "311-120CRCT-ND")
        (field (name "MANUFACTURER_PART_NUMBER") "RC0805FR-07120RL")
      )
      (libsource (lib "altium-import") (part "root_1_120_"))
    )
    (comp (ref "R47")
      (value "1k")
      (fields
        (field (name "DIGIKEY PART NUMBER") "311-1.00KCRCT-ND")
        (field (name "MANUFACTURER_PART_NUMBER") "RC0805FR-071KL")
      )
      (libsource (lib "altium-import") (part "root_0_1k_"))
    )
    (comp (ref "R48")
      (value "1k")
      (fields
        (field (name "DIGIKEY PART NUMBER") "311-1.00KCRCT-ND")
        (field (name "MANUFACTURER_PART_NUMBER") "RC0805FR-071KL")
      )
      (libsource (lib "altium-import") (part "root_0_1k_"))
    )
    (comp (ref "R49")
      (value "100k")
      (fields
        (field (name "DIGIKEY PART NUMBER") "311-100KCRCT-ND")
        (field (name "MANUFACTURER_PART_NUMBER") "RC0805FR-07100KL")
      )
      (libsource (lib "altium-import") (part "root_0_100k_"))
    )
    (comp (ref "R50")
      (value "100k")
      (fields
        (field (name "DIGIKEY PART NUMBER") "311-100KCRCT-ND")
        (field (name "MANUFACTURER_PART_NUMBER") "RC0805FR-07100KL")
      )
      (libsource (lib "altium-import") (part "root_0_100k_"))
    )
    (comp (ref "R51")
      (value "10k")
      (fields
        (field (name "DIGIKEY PART NUMBER") "311-10KARCT-ND")
        (field (name "MANUFACTURER_PART_NUMBER") "RC0805JR-0710KL")
      )
      (libsource (lib "altium-import") (part "root_0_10k_"))
    )
    (comp (ref "R52")
      (value "2k")
      (fields
        (field (name "DIGIKEY PART NUMBER") "311-2.00KCRCT-ND")
        (field (name "MANUFACTURER_PART_NUMBER") "RC0805FR-072KL")
      )
      (libsource (lib "altium-import") (part "root_0_2k_"))
    )
    (comp (ref "R53")
      (value "1k")
      (fields
        (field (name "DIGIKEY PART NUMBER") "311-1.00KCRCT-ND")
        (field (name "MANUFACTURER_PART_NUMBER") "RC0805FR-071KL")
      )
      (libsource (lib "altium-import") (part "root_0_1k_"))
    )
    (comp (ref "R54")
      (value "1k")
      (fields
        (field (name "MANUFACTURER_PART_NUMBER") "RC0805FR-071KL")
        (field (name "DIGIKEY PART NUMBER") "311-1.00KCRCT-ND")
      )
      (libsource (lib "") (part "root_0_1k__1"))
    )
    (comp (ref "R55")
      (value "470")
      (fields
        (field (name "MANUFACTURER_PART_NUMBER") "ERJ-6ENF4700V")
        (field (name "DIGIKEY PART NUMBER") "P470CCT-ND")
      )
      (libsource (lib "") (part "root_0_470__2"))
    )
    (comp (ref "R56")
      (value "1k")
      (fields
        (field (name "DIGIKEY PART NUMBER") "311-1.00KCRCT-ND")
        (field (name "MANUFACTURER_PART_NUMBER") "RC0805FR-071KL")
      )
      (libsource (lib "altium-import") (part "root_0_1k_"))
    )
    (comp (ref "R57")
      (value "1k")
      (fields
        (field (name "DIGIKEY PART NUMBER") "311-1.00KCRCT-ND")
        (field (name "MANUFACTURER_PART_NUMBER") "RC0805FR-071KL")
      )
      (libsource (lib "altium-import") (part "root_0_1k_"))
    )
    (comp (ref "R59")
      (value "10K")
      (fields (field (name "MANUFACTURER") "YAGEO") (field (name "MANUFACTURER PART") "RC0805FR-072K74L"))
      (libsource (lib "altium-import") (part "root_3_10K_"))
    )
    (comp (ref "R60")
      (value "100k")
      (fields
        (field (name "DIGIKEY PART NUMBER") "311-100KCRCT-ND")
        (field (name "MANUFACTURER_PART_NUMBER") "RC0805FR-07100KL")
      )
      (libsource (lib "altium-import") (part "root_0_100k_"))
    )
    (comp (ref "R61")
      (value "100k")
      (fields
        (field (name "DIGIKEY PART NUMBER") "311-100KCRCT-ND")
        (field (name "MANUFACTURER_PART_NUMBER") "RC0805FR-07100KL")
      )
      (libsource (lib "altium-import") (part "root_0_100k_"))
    )
    (comp (ref "R62")
      (value "470")
      (fields
        (field (name "MANUFACTURER_PART_NUMBER") "ERJ-6ENF4700V")
        (field (name "DIGIKEY PART NUMBER") "P470CCT-ND")
      )
      (libsource (lib "altium-import") (part "root_0_470_"))
    )
    (comp (ref "R63")
      (value "470")
      (fields
        (field (name "MANUFACTURER_PART_NUMBER") "ERJ-6ENF4700V")
        (field (name "DIGIKEY PART NUMBER") "P470CCT-ND")
      )
      (libsource (lib "") (part "root_0_470__1"))
    )
    (comp (ref "SW3")
      (value "RST")
      (fields
        (field (name "MANUFACTURER PART") "BDSwitch-2pin-1CH-1r27-SMD-V")
        (field (name "CONTRIBUTOR") "lcsc")
      )
      (libsource (lib "altium-import") (part "root_0_RST_"))
    )
    (comp (ref "U2")
      (value "TC4424A")
      (fields
        (field (name "DIGIKEY PART NUMBER") "212-IXDN602SIACT-ND")
        (field (name "MANUFACTURER_PART_NUMBER") "IXDN602SIATR")
      )
      (libsource (lib "altium-import") (part "root_0_TC4424A_"))
    )
    (comp (ref "U4")
      (value "TC4424A")
      (fields
        (field (name "DIGIKEY PART NUMBER") "212-IXDN602SIACT-ND")
        (field (name "MANUFACTURER_PART_NUMBER") "IXDN602SIATR")
      )
      (libsource (lib "altium-import") (part "root_0_TC4424A_"))
    )
    (comp (ref "U5")
      (value "MPX4250")
      (fields
        (field (name "DIGIKEY PART NUMBER") "MPX4250AP-ND")
        (field (name "MANUFACTURER_PART_NUMBER") "MPX4250AP")
      )
      (libsource (lib "altium-import") (part "root_0_MPX4250_"))
    )
    (comp (ref "U6")
      (value "SP720")
      (fields
        (field (name "DIGIKEY PART NUMBER") "F3162CT-ND")
        (field (name "MANUFACTURER_PART_NUMBER") "SP720ABTG")
      )
      (libsource (lib "altium-import") (part "root_0_SP720_"))
    )
    (comp (ref "U7")
      (value "Header")
      (fields (field (name "MANUFACTURER PART") "Male Header 2 pin") (field (name "CONTRIBUTOR") "amir slz"))
      (libsource (lib "altium-import") (part "root_3_Header_"))
    )
    (comp (ref "U8")
      (value "Header")
      (fields (field (name "MANUFACTURER PART") "Male Header 2 pin") (field (name "CONTRIBUTOR") "amir slz"))
      (libsource (lib "altium-import") (part "root_1_Header_"))
    )
    (comp (ref "U10")
      (value "IDC2.54-2-10")
      (fields
        (field (name "MANUFACTURER") "Megastar(兆星)")
        (field (name "MANUFACTURER PART") "ZX-IDC2.54-2-10PZZ")
        (field (name "CONTRIBUTOR") "lcsc")
      )
      (libsource (lib "altium-import") (part "root_0_IDC2.54-2-10_"))
    )
    (comp (ref "U13")
      (value "Power Input")
      (fields
        (field (name "MANUFACTURER") "ReliaPro")
        (field (name "MANUFACTURER PART") "PH-12AW")
        (field (name "CONTRIBUTOR") "amir slz")
      )
      (libsource (lib "altium-import") (part "root_0_Power Input_"))
    )
    (comp (ref "XA1")
      (value "Arduino_Mega2560_Shield")
      (libsource (lib "altium-import") (part "root_0_Arduino_Mega2560_Shield_"))
    )
  )
  (nets
    (net (code "1") (name "/12V-SW") (class "Default")
      (node (ref "A1") (pin "8") (pinfunction "VMOT_8") (pintype "passive"))
      (node (ref "AAAA1") (pin "IN+") (pinfunction "IN+_IN+") (pintype "passive"))
      (node (ref "AAAAD1") (pin "2") (pinfunction "A_2") (pintype "passive"))
      (node (ref "D16") (pin "1") (pinfunction "K_1") (pintype "passive"))
      (node (ref "D17") (pin "1") (pinfunction "K_1") (pintype "passive"))
      (node (ref "D18") (pin "1") (pinfunction "K_1") (pintype "passive"))
      (node (ref "D19") (pin "1") (pinfunction "K_1") (pintype "passive"))
      (node (ref "J8") (pin "1") (pinfunction "Pin_1_1") (pintype "passive"))
      (node (ref "J8") (pin "2") (pinfunction "Pin_2_2") (pintype "passive"))
      (node (ref "J8") (pin "3") (pinfunction "Pin_3_3") (pintype "passive"))
      (node (ref "JP1") (pin "3") (pinfunction "B_3") (pintype "passive"))
      (node (ref "R10") (pin "2") (pintype "passive"))
      (node (ref "R23") (pin "2") (pintype "passive"))
      (node (ref "R24") (pin "2") (pintype "passive"))
      (node (ref "R30") (pin "2") (pintype "passive"))
      (node (ref "R51") (pin "2") (pintype "passive"))
      (node (ref "R9") (pin "2") (pintype "passive"))
      (node (ref "U13") (pin "1") (pinfunction "1_1") (pintype "passive"))
    )
    (net (code "2") (name "/BOOST-OUT") (class "Default")
      (node (ref "D17") (pin "2") (pinfunction "A_2") (pintype "passive"))
      (node (ref "J4") (pin "12") (pinfunction "Pin_12_12") (pintype "passive"))
      (node (ref "Q10") (pin "2") (pinfunction "D_2") (pintype "passive"))
    )
    (net (code "3") (name "/CAM-IN") (class "Default")
      (node (ref "J4") (pin "34") (pinfunction "Pin_34_34") (pintype "passive"))
      (node (ref "JP3") (pin "2") (pinfunction "C_2") (pintype "passive"))
      (node (ref "JP5") (pin "1") (pinfunction "A_1") (pintype "passive"))
    )
    (net (code "4") (name "/CLT_Sensor") (class "Default")
      (node (ref "C11") (pin "1") (pintype "passive"))
      (node (ref "J4") (pin "37") (pinfunction "Pin_37_37") (pintype "passive"))
      (node (ref "R36") (pin "1") (pintype "passive"))
      (node (ref "R40") (pin "2") (pintype "passive"))
    )
    (net (code "5") (name "/CRANK-IN") (class "Default")
      (node (ref "J4") (pin "32") (pinfunction "Pin_32_32") (pintype "passive"))
      (node (ref "JP2") (pin "2") (pinfunction "C_2") (pintype "passive"))
      (node (ref "JP4") (pin "1") (pinfunction "A_1") (pintype "passive"))
    )
    (net (code "6") (name "/Clutch_in") (class "Default")
      (node (ref "JP9") (pin "1") (pinfunction "1_1") (pintype "passive"))
      (node (ref "R37") (pin "1") (pintype "passive"))
    )
    (net (code "7") (name "/FAN-OUT") (class "Default")
      (node (ref "JP6") (pin "1") (pinfunction "1_1") (pintype "passive"))
      (node (ref "Q2") (pin "3") (pinfunction "D_3") (pintype "passive"))
    )
    (net (code "8") (name "/FUELPUMP-OUT") (class "Default")
      (node (ref "JP7") (pin "1") (pinfunction "1_1") (pintype "passive"))
      (node (ref "Q3") (pin "3") (pinfunction "D_3") (pintype "passive"))
    )
    (net (code "9") (name "/HC-1-OUT") (class "Default")
      (node (ref "D18") (pin "2") (pinfunction "A_2") (pintype "passive"))
      (node (ref "J4") (pin "10") (pinfunction "Pin_10_10") (pintype "passive"))
      (node (ref "Q11") (pin "2") (pinfunction "D_2") (pintype "passive"))
    )
    (net (code "10") (name "/HC-2-OUT") (class "Default")
      (node (ref "D16") (pin "2") (pinfunction "A_2") (pintype "passive"))
      (node (ref "J4") (pin "6") (pinfunction "Pin_6_6") (pintype "passive"))
      (node (ref "Q8") (pin "2") (pinfunction "D_2") (pintype "passive"))
    )
    (net (code "11") (name "/IAT_Sensor") (class "Default")
      (node (ref "C10") (pin "1") (pintype "passive"))
      (node (ref "J4") (pin "39") (pinfunction "Pin_39_39") (pintype "passive"))
      (node (ref "R35") (pin "1") (pintype "passive"))
      (node (ref "R39") (pin "2") (pintype "passive"))
    )
    (net (code "12") (name "/IDLE-OUT") (class "Default")
      (node (ref "D19") (pin "2") (pinfunction "A_2") (pintype "passive"))
      (node (ref "J4") (pin "8") (pinfunction "Pin_8_8") (pintype "passive"))
      (node (ref "Q9") (pin "2") (pinfunction "D_2") (pintype "passive"))
    )
    (net (code "13") (name "/IGN-1-OUT") (class "Default")
      (node (ref "J4") (pin "13") (pinfunction "Pin_13_13") (pintype "passive"))
      (node (ref "R14") (pin "1") (pintype "passive"))
    )
    (net (code "14") (name "/IGN-2-OUT") (class "Default")
      (node (ref "J4") (pin "14") (pinfunction "Pin_14_14") (pintype "passive"))
      (node (ref "R13") (pin "1") (pintype "passive"))
    )
    (net (code "15") (name "/IGN-3-OUT") (class "Default")
      (node (ref "J4") (pin "16") (pinfunction "Pin_16_16") (pintype "passive"))
      (node (ref "R28") (pin "1") (pintype "passive"))
    )
    (net (code "16") (name "/IGN-4-OUT") (class "Default")
      (node (ref "J4") (pin "15") (pinfunction "Pin_15_15") (pintype "passive"))
      (node (ref "R27") (pin "1") (pintype "passive"))
    )
    (net (code "17") (name "/INJ-1-OUT") (class "Default")
      (node (ref "D5") (pin "1") (pinfunction "K_1") (pintype "passive"))
      (node (ref "J4") (pin "1") (pinfunction "Pin_1_1") (pintype "passive"))
      (node (ref "J4") (pin "2") (pinfunction "Pin_2_2") (pintype "passive"))
      (node (ref "Q4") (pin "2") (pinfunction "D_2") (pintype "passive"))
    )
    (net (code "18") (name "/INJ-2-OUT") (class "Default")
      (node (ref "D11") (pin "1") (pinfunction "K_1") (pintype "passive"))
      (node (ref "J4") (pin "3") (pinfunction "Pin_3_3") (pintype "passive"))
      (node (ref "J4") (pin "4") (pinfunction "Pin_4_4") (pintype "passive"))
      (node (ref "Q7") (pin "2") (pinfunction "D_2") (pintype "passive"))
    )
    (net (code "19") (name "/INJ-3-OUT") (class "Default")
      (node (ref "D12") (pin "1") (pinfunction "K_1") (pintype "passive"))
      (node (ref "J4") (pin "5") (pinfunction "Pin_5_5") (pintype "passive"))
      (node (ref "J4") (pin "7") (pinfunction "Pin_7_7") (pintype "passive"))
      (node (ref "Q6") (pin "2") (pinfunction "D_2") (pintype "passive"))
    )
    (net (code "20") (name "/INJ-4-OUT") (class "Default")
      (node (ref "D6") (pin "1") (pinfunction "K_1") (pintype "passive"))
      (node (ref "J4") (pin "11") (pinfunction "Pin_11_11") (pintype "passive"))
      (node (ref "J4") (pin "9") (pinfunction "Pin_9_9") (pintype "passive"))
      (node (ref "Q5") (pin "2") (pinfunction "D_2") (pintype "passive"))
    )
    (net (code "21") (name "/MAP-EXT") (class "Default")
      (node (ref "J4") (pin "21") (pinfunction "Pin_21_21") (pintype "passive"))
      (node (ref "JP11") (pin "1") (pinfunction "A_1") (pintype "passive"))
      (node (ref "R34") (pin "2") (pintype "passive"))
    )
    (net (code "22") (name "/MCU-A0") (class "Default")
      (node (ref "C13") (pin "1") (pintype "passive"))
      (node (ref "R39") (pin "1") (pintype "passive"))
      (node (ref "U6") (pin "5") (pinfunction "I5_5") (pintype "passive"))
      (node (ref "XA1") (pin "A0") (pinfunction "A0_A0") (pintype "passive"))
    )
    (net (code "23") (name "/MCU-A1") (class "Default")
      (node (ref "C14") (pin "1") (pintype "passive"))
      (node (ref "R40") (pin "1") (pintype "passive"))
      (node (ref "U6") (pin "3") (pinfunction "I3_3") (pintype "passive"))
      (node (ref "XA1") (pin "A1") (pinfunction "A1_A1") (pintype "passive"))
    )
    (net (code "24") (name "/MCU-A2") (class "Default")
      (node (ref "C12") (pin "1") (pintype "passive"))
      (node (ref "R38") (pin "1") (pintype "passive"))
      (node (ref "U6") (pin "4") (pinfunction "I4_4") (pintype "passive"))
      (node (ref "XA1") (pin "A2") (pinfunction "A2_A2") (pintype "passive"))
    )
    (net (code "25") (name "/MCU-A3") (class "Default")
      (node (ref "C8") (pin "2") (pintype "passive"))
      (node (ref "R34") (pin "1") (pintype "passive"))
      (node (ref "U6") (pin "2") (pinfunction "I2_2") (pintype "passive"))
      (node (ref "XA1") (pin "A3") (pinfunction "A3_A3") (pintype "passive"))
    )
    (net (code "26") (name "/MCU-A4") (class "Default")
      (node (ref "C7") (pin "1") (pintype "passive"))
      (node (ref "D20") (pin "1") (pinfunction "K_1") (pintype "passive"))
      (node (ref "R32") (pin "1") (pintype "passive"))
      (node (ref "U6") (pin "1") (pinfunction "I1_1") (pintype "passive"))
      (node (ref "XA1") (pin "A4") (pinfunction "A4_A4") (pintype "passive"))
    )
    (net (code "27") (name "/MCU-A5") (class "Default")
      (node (ref "C29") (pin "1") (pintype "passive"))
      (node (ref "R55") (pin "1") (pintype "passive"))
      (node (ref "XA1") (pin "A5") (pinfunction "A5_A5") (pintype "passive"))
    )
    (net (code "28") (name "/MCU-A8") (class "Default")
      (node (ref "C6") (pin "1") (pintype "passive"))
      (node (ref "R31") (pin "1") (pintype "passive"))
      (node (ref "U6") (pin "6") (pinfunction "I6_6") (pintype "passive"))
      (node (ref "XA1") (pin "A8") (pinfunction "A8_A8") (pintype "passive"))
    )
    (net (code "29") (name "/MCU-A9") (class "Default")
      (node (ref "C23") (pin "1") (pintype "passive"))
      (node (ref "R63") (pin "1") (pintype "passive"))
      (node (ref "XA1") (pin "A9") (pinfunction "A9_A9") (pintype "passive"))
    )
    (net (code "30") (name "/MCU-A10") (class "Default")
      (node (ref "C22") (pin "1") (pintype "passive"))
      (node (ref "R62") (pin "2") (pintype "passive"))
      (node (ref "XA1") (pin "A10") (pinfunction "A10_A10") (pintype "passive"))
    )
    (net (code "31") (name "/MCU-D0") (class "Default")
      (node (ref "J2") (pin "4") (pinfunction "Pin_4_4") (pintype "passive"))
      (node (ref "XA1") (pin "D0") (pinfunction "D0_RX0_D0") (pintype "passive"))
    )
    (net (code "32") (name "/MCU-D1") (class "Default")
      (node (ref "R53") (pin "1") (pintype "passive"))
      (node (ref "XA1") (pin "D1") (pinfunction "D1_TX0_D1") (pintype "passive"))
    )
    (net (code "33") (name "/MCU-D2{slash}FlexSensor") (class "Default")
      (node (ref "C5") (pin "1") (pintype "passive"))
      (node (ref "JP12") (pin "1") (pinfunction "1_1") (pintype "passive"))
      (node (ref "R33") (pin "2") (pintype "passive"))
      (node (ref "U6") (pin "11") (pinfunction "I10_11") (pintype "passive"))
      (node (ref "XA1") (pin "D2") (pinfunction "D2_INT0_D2") (pintype "passive"))
    )
    (net (code "34") (name "/MCU-D3") (class "Default")
      (node (ref "J2") (pin "1") (pinfunction "Pin_1_1") (pintype "passive"))
      (node (ref "XA1") (pin "D3") (pinfunction "D3_INT1_D3") (pintype "passive"))
    )
    (net (code "35") (name "/MCU-D4") (class "Default")
      (node (ref "R57") (pin "2") (pintype "passive"))
      (node (ref "R61") (pin "2") (pintype "passive"))
      (node (ref "XA1") (pin "D4") (pinfunction "D4_D4") (pintype "passive"))
    )
    (net (code "36") (name "/MCU-D5") (class "Default")
      (node (ref "R56") (pin "2") (pintype "passive"))
      (node (ref "R60") (pin "1") (pintype "passive"))
      (node (ref "XA1") (pin "D5") (pinfunction "D5_D5") (pintype "passive"))
    )
    (net (code "37") (name "/MCU-D6") (class "Default")
      (node (ref "R48") (pin "2") (pintype "passive"))
      (node (ref "R50") (pin "2") (pintype "passive"))
      (node (ref "XA1") (pin "D6") (pinfunction "D6_D6") (pintype "passive"))
    )
    (net (code "38") (name "/MCU-D7") (class "Default")
      (node (ref "R47") (pin "2") (pintype "passive"))
      (node (ref "R49") (pin "1") (pintype "passive"))
      (node (ref "XA1") (pin "D7") (pinfunction "D7_D7") (pintype "passive"))
    )
    (net (code "39") (name "/MCU-D8") (class "Default")
      (node (ref "R1") (pin "1") (pintype "passive"))
      (node (ref "R5") (pin "2") (pintype "passive"))
      (node (ref "XA1") (pin "D8") (pinfunction "D8_D8") (pintype "passive"))
    )
    (net (code "40") (name "/MCU-D9") (class "Default")
      (node (ref "R15") (pin "1") (pintype "passive"))
      (node (ref "R17") (pin "2") (pintype "passive"))
      (node (ref "XA1") (pin "D9") (pinfunction "D9_D9") (pintype "passive"))
    )
    (net (code "41") (name "/MCU-D10") (class "Default")
      (node (ref "R16") (pin "2") (pintype "passive"))
      (node (ref "R18") (pin "2") (pintype "passive"))
      (node (ref "XA1") (pin "D10") (pinfunction "D10_D10") (pintype "passive"))
    )
    (net (code "42") (name "/MCU-D11") (class "Default")
      (node (ref "R2") (pin "2") (pintype "passive"))
      (node (ref "R6") (pin "2") (pintype "passive"))
      (node (ref "XA1") (pin "D11") (pinfunction "D11_D11") (pintype "passive"))
    )
    (net (code "43") (name "/MCU-D16") (class "Default")
      (node (ref "A1") (pin "16") (pinfunction "DIR_16") (pintype "passive"))
      (node (ref "XA1") (pin "D16") (pinfunction "D16_TX2_D16") (pintype "passive"))
    )
    (net (code "44") (name "/MCU-D17") (class "Default")
      (node (ref "A1") (pin "15") (pinfunction "STEP_15") (pintype "passive"))
      (node (ref "XA1") (pin "D17") (pinfunction "D17_RX2_D17") (pintype "passive"))
    )
    (net (code "45") (name "/MCU-D18") (class "Default")
      (node (ref "C16") (pin "2") (pintype "passive"))
      (node (ref "IC3") (pin "7") (pinfunction "Pin_7_7") (pintype "passive"))
      (node (ref "R44") (pin "1") (pintype "passive"))
      (node (ref "U6") (pin "9") (pinfunction "I8_9") (pintype "passive"))
      (node (ref "XA1") (pin "D18") (pinfunction "D18_TX1_D18") (pintype "passive"))
    )
    (net (code "46") (name "/MCU-D19") (class "Default")
      (node (ref "C15") (pin "2") (pintype "passive"))
      (node (ref "IC3") (pin "8") (pinfunction "Pin_8_8") (pintype "passive"))
      (node (ref "R43") (pin "1") (pintype "passive"))
      (node (ref "U6") (pin "10") (pinfunction "I9_10") (pintype "passive"))
      (node (ref "XA1") (pin "D19") (pinfunction "D19_RX1_D19") (pintype "passive"))
    )
    (net (code "47") (name "/MCU-D20{slash}VSS") (class "Default")
      (node (ref "C28") (pin "2") (pintype "passive"))
      (node (ref "J5") (pin "4") (pinfunction "Pin_4_4") (pintype "passive"))
      (node (ref "R54") (pin "1") (pintype "passive"))
      (node (ref "XA1") (pin "D20") (pinfunction "D20_SDA_D20") (pintype "passive"))
    )
    (net (code "48") (name "/MCU-D21") (class "Default")
      (node (ref "J5") (pin "3") (pinfunction "Pin_3_3") (pintype "passive"))
      (node (ref "XA1") (pin "D21") (pinfunction "D21_SCL_D21") (pintype "passive"))
    )
    (net (code "49") (name "/MCU-D24") (class "Default")
      (node (ref "A1") (pin "9") (pinfunction "EN_9") (pintype "passive"))
      (node (ref "XA1") (pin "D24") (pinfunction "D24_D24") (pintype "passive"))
    )
    (net (code "50") (name "/MCU-D38") (class "Default")
      (node (ref "R3") (pin "1") (pintype "passive"))
      (node (ref "R7") (pin "2") (pintype "passive"))
      (node (ref "XA1") (pin "D38") (pinfunction "D38_D38") (pintype "passive"))
    )
    (net (code "51") (name "/MCU-D40") (class "Default")
      (node (ref "R4") (pin "2") (pintype "passive"))
      (node (ref "R8") (pin "2") (pintype "passive"))
      (node (ref "XA1") (pin "D40") (pinfunction "D40_D40") (pintype "passive"))
    )
    (net (code "52") (name "/MCU-D45") (class "Default")
      (node (ref "Q3") (pin "1") (pinfunction "G_1") (pintype "passive"))
      (node (ref "XA1") (pin "D45") (pinfunction "D45_D45") (pintype "passive"))
    )
    (net (code "53") (name "/MCU-D47") (class "Default")
      (node (ref "Q2") (pin "1") (pinfunction "G_1") (pintype "passive"))
      (node (ref "XA1") (pin "D47") (pinfunction "D47_D47") (pintype "passive"))
    )
    (net (code "54") (name "/MCU-D49") (class "Default")
      (node (ref "Q1") (pin "1") (pinfunction "G_1") (pintype "passive"))
      (node (ref "XA1") (pin "D49") (pinfunction "D49_D49") (pintype "passive"))
    )
    (net (code "55") (name "/MCU-D50") (class "Default")
      (node (ref "R19") (pin "1") (pintype "passive"))
      (node (ref "R21") (pin "2") (pintype "passive"))
      (node (ref "XA1") (pin "D50") (pinfunction "D50_D50") (pintype "passive"))
    )
    (net (code "56") (name "/MCU-D51") (class "Default")
      (node (ref "D13") (pin "1") (pinfunction "K_1") (pintype "passive"))
      (node (ref "R37") (pin "2") (pintype "passive"))
      (node (ref "U6") (pin "14") (pinfunction "I13_14") (pintype "passive"))
      (node (ref "XA1") (pin "D51") (pinfunction "D51_D51") (pintype "passive"))
    )
    (net (code "57") (name "/MCU-D52") (class "Default")
      (node (ref "R20") (pin "2") (pintype "passive"))
      (node (ref "R22") (pin "2") (pintype "passive"))
      (node (ref "XA1") (pin "D52") (pinfunction "D52_D52") (pintype "passive"))
    )
    (net (code "58") (name "/O2_Sensor") (class "Default")
      (node (ref "C3") (pin "1") (pintype "passive"))
      (node (ref "J4") (pin "40") (pinfunction "Pin_40_40") (pintype "passive"))
      (node (ref "R31") (pin "2") (pintype "passive"))
    )
    (net (code "59") (name "/PROTO-1") (class "Default")
      (node (ref "J4") (pin "27") (pinfunction "Pin_27_27") (pintype "passive"))
      (node (ref "J7") (pin "1") (pinfunction "Pin_1_1") (pintype "passive"))
      (node (ref "JP12") (pin "2") (pinfunction "2_2") (pintype "passive"))
    )
    (net (code "60") (name "/PROTO-2") (class "Default")
      (node (ref "J4") (pin "29") (pinfunction "Pin_29_29") (pintype "passive"))
      (node (ref "J7") (pin "2") (pinfunction "Pin_2_2") (pintype "passive"))
      (node (ref "JP6") (pin "2") (pinfunction "2_2") (pintype "passive"))
    )
    (net (code "61") (name "/PROTO-3") (class "Default")
      (node (ref "J4") (pin "31") (pinfunction "Pin_31_31") (pintype "passive"))
      (node (ref "J7") (pin "3") (pinfunction "Pin_3_3") (pintype "passive"))
      (node (ref "JP7") (pin "2") (pinfunction "2_2") (pintype "passive"))
    )
    (net (code "62") (name "/PROTO-4") (class "Default")
      (node (ref "J4") (pin "33") (pinfunction "Pin_33_33") (pintype "passive"))
      (node (ref "J7") (pin "4") (pinfunction "Pin_4_4") (pintype "passive"))
      (node (ref "JP8") (pin "2") (pinfunction "2_2") (pintype "passive"))
    )
    (net (code "63") (name "/PROTO-5") (class "Default")
      (node (ref "J4") (pin "35") (pinfunction "Pin_35_35") (pintype "passive"))
      (node (ref "J7") (pin "5") (pinfunction "Pin_5_5") (pintype "passive"))
      (node (ref "JP9") (pin "2") (pinfunction "2_2") (pintype "passive"))
    )
    (net (code "64") (name "/RESET") (class "Default")
      (node (ref "R46") (pin "1") (pintype "passive"))
      (node (ref "R59") (pin "2") (pinfunction "2_2") (pintype "passive"))
      (node (ref "XA1") (pin "RST1") (pinfunction "RESET_RST1") (pintype "passive"))
    )
    (net (code "65") (name "/STEP-A1") (class "Default")
      (node (ref "A1") (pin "4") (pinfunction "A1_4") (pintype "passive"))
      (node (ref "J4") (pin "20") (pinfunction "Pin_20_20") (pintype "passive"))
    )
    (net (code "66") (name "/STEP-A2") (class "Default")
      (node (ref "A1") (pin "3") (pinfunction "A2_3") (pintype "passive"))
      (node (ref "J4") (pin "18") (pinfunction "Pin_18_18") (pintype "passive"))
    )
    (net (code "67") (name "/STEP-B1") (class "Default")
      (node (ref "A1") (pin "5") (pinfunction "B1_5") (pintype "passive"))
      (node (ref "J4") (pin "22") (pinfunction "Pin_22_22") (pintype "passive"))
    )
    (net (code "68") (name "/STEP-B2") (class "Default")
      (node (ref "A1") (pin "6") (pinfunction "B2_6") (pintype "passive"))
      (node (ref "J4") (pin "24") (pinfunction "Pin_24_24") (pintype "passive"))
    )
    (net (code "69") (name "/TACHO-OUT") (class "Default")
      (node (ref "JP8") (pin "1") (pinfunction "1_1") (pintype "passive"))
      (node (ref "Q1") (pin "3") (pinfunction "D_3") (pintype "passive"))
      (node (ref "R51") (pin "1") (pintype "passive"))
    )
    (net (code "70") (name "/TPS_Sensor") (class "Default")
      (node (ref "C9") (pin "1") (pintype "passive"))
      (node (ref "J4") (pin "38") (pinfunction "Pin_38_38") (pintype "passive"))
      (node (ref "R38") (pin "2") (pintype "passive"))
    )
    (net (code "71") (name "/VR1-") (class "Default")
      (node (ref "IC3") (pin "1") (pinfunction "Pin_1_1") (pintype "passive"))
      (node (ref "J4") (pin "28") (pinfunction "Pin_28_28") (pintype "passive"))
    )
    (net (code "72") (name "/VR2-") (class "Default")
      (node (ref "IC3") (pin "4") (pinfunction "Pin_4_4") (pintype "passive"))
      (node (ref "J4") (pin "30") (pinfunction "Pin_30_30") (pintype "passive"))
    )
    (net (code "73") (name "/VRegIn") (class "Default")
      (node (ref "AAAAC4") (pin "1") (pinfunction "1_1") (pintype "passive"))
      (node (ref "AAAAC6") (pin "2") (pinfunction "2_2") (pintype "passive"))
      (node (ref "AAAAD1") (pin "1") (pinfunction "K_1") (pintype "passive"))
      (node (ref "AAAAU8") (pin "1") (pinfunction "Vin_1") (pintype "passive"))
    )
    (net (code "74") (name "GND") (class "Default")
      (node (ref "A1") (pin "1") (pinfunction "GND_1") (pintype "passive"))
      (node (ref "A1") (pin "7") (pinfunction "GND_7") (pintype "passive"))
      (node (ref "AAAA1") (pin "IN-") (pinfunction "IN-_IN-") (pintype "passive"))
      (node (ref "AAAA1") (pin "OUT-") (pinfunction "OUT-_OUT-") (pintype "passive"))
      (node (ref "AAAAC3") (pin "2") (pinfunction "2_2") (pintype "passive"))
      (node (ref "AAAAC4") (pin "2") (pinfunction "2_2") (pintype "passive"))
      (node (ref "AAAAC5") (pin "1") (pinfunction "1_1") (pintype "passive"))
      (node (ref "AAAAC6") (pin "1") (pinfunction "1_1") (pintype "passive"))
      (node (ref "AAAAD5") (pin "2") (pinfunction "A_2") (pintype "passive"))
      (node (ref "AAAALED8") (pin "2") (pinfunction "C_2") (pintype "passive"))
      (node (ref "AAAAR14") (pin "1") (pinfunction "1_1") (pintype "passive"))
      (node (ref "AAAAU8") (pin "3") (pinfunction "Gnd_3") (pintype "passive"))
      (node (ref "AAAAU8") (pin "5") (pinfunction "ON#/OFF_5") (pintype "passive"))
      (node (ref "AAAAU8") (pin "6") (pinfunction "TAB_6") (pintype "passive"))
      (node (ref "C1") (pin "1") (pintype "passive"))
      (node (ref "C10") (pin "2") (pintype "passive"))
      (node (ref "C11") (pin "2") (pintype "passive"))
      (node (ref "C12") (pin "2") (pintype "passive"))
      (node (ref "C13") (pin "2") (pintype "passive"))
      (node (ref "C14") (pin "2") (pintype "passive"))
      (node (ref "C15") (pin "1") (pintype "passive"))
      (node (ref "C16") (pin "1") (pintype "passive"))
      (node (ref "C17") (pin "1") (pintype "passive"))
      (node (ref "C2") (pin "1") (pintype "passive"))
      (node (ref "C22") (pin "2") (pintype "passive"))
      (node (ref "C23") (pin "2") (pintype "passive"))
      (node (ref "C24") (pin "1") (pintype "passive"))
      (node (ref "C25") (pin "1") (pintype "passive"))
      (node (ref "C26") (pin "1") (pintype "passive"))
      (node (ref "C27") (pin "1") (pintype "passive"))
      (node (ref "C28") (pin "1") (pintype "passive"))
      (node (ref "C29") (pin "2") (pintype "passive"))
      (node (ref "C3") (pin "2") (pintype "passive"))
      (node (ref "C4") (pin "2") (pintype "passive"))
      (node (ref "C5") (pin "2") (pintype "passive"))
      (node (ref "C6") (pin "2") (pintype "passive"))
      (node (ref "C7") (pin "2") (pintype "passive"))
      (node (ref "C8") (pin "1") (pintype "passive"))
      (node (ref "C9") (pin "2") (pintype "passive"))
      (node (ref "D10") (pin "1") (pinfunction "K_1") (pintype "passive"))
      (node (ref "D13") (pin "2") (pinfunction "A_2") (pintype "passive"))
      (node (ref "D2") (pin "1") (pinfunction "K_1") (pintype "passive"))
      (node (ref "D20") (pin "2") (pinfunction "A_2") (pintype "passive"))
      (node (ref "D9") (pin "1") (pinfunction "K_1") (pintype "passive"))
      (node (ref "IC3") (pin "6") (pinfunction "Pin_6_6") (pintype "passive"))
      (node (ref "J2") (pin "3") (pinfunction "Pin_3_3") (pintype "passive"))
      (node (ref "J4") (pin "17") (pinfunction "Pin_17_17") (pintype "passive"))
      (node (ref "J4") (pin "19") (pinfunction "Pin_19_19") (pintype "passive"))
      (node (ref "J4") (pin "23") (pinfunction "Pin_23_23") (pintype "passive"))
      (node (ref "J4") (pin "36") (pinfunction "Pin_36_36") (pintype "passive"))
      (node (ref "J6") (pin "1") (pinfunction "Pin_1_1") (pintype "passive"))
      (node (ref "J6") (pin "2") (pinfunction "Pin_2_2") (pintype "passive"))
      (node (ref "J6") (pin "3") (pinfunction "Pin_3_3") (pintype "passive"))
      (node (ref "J6") (pin "4") (pinfunction "Pin_4_4") (pintype "passive"))
      (node (ref "J6") (pin "5") (pinfunction "Pin_5_5") (pintype "passive"))
      (node (ref "Q1") (pin "2") (pinfunction "S_2") (pintype "passive"))
      (node (ref "Q10") (pin "3") (pinfunction "S_3") (pintype "passive"))
      (node (ref "Q11") (pin "3") (pinfunction "S_3") (pintype "passive"))
      (node (ref "Q2") (pin "2") (pinfunction "S_2") (pintype "passive"))
      (node (ref "Q3") (pin "2") (pinfunction "S_2") (pintype "passive"))
      (node (ref "Q4") (pin "3") (pinfunction "S_3") (pintype "passive"))
      (node (ref "Q5") (pin "3") (pinfunction "S_3") (pintype "passive"))
      (node (ref "Q6") (pin "3") (pinfunction "S_3") (pintype "passive"))
      (node (ref "Q7") (pin "3") (pinfunction "S_3") (pintype "passive"))
      (node (ref "Q8") (pin "3") (pinfunction "S_3") (pintype "passive"))
      (node (ref "Q9") (pin "3") (pinfunction "S_3") (pintype "passive"))
      (node (ref "R1") (pin "2") (pintype "passive"))
      (node (ref "R15") (pin "2") (pintype "passive"))
      (node (ref "R16") (pin "1") (pintype "passive"))
      (node (ref "R19") (pin "2") (pintype "passive"))
      (node (ref "R2") (pin "1") (pintype "passive"))
      (node (ref "R20") (pin "1") (pintype "passive"))
      (node (ref "R29") (pin "1") (pintype "passive"))
      (node (ref "R3") (pin "2") (pintype "passive"))
      (node (ref "R4") (pin "1") (pintype "passive"))
      (node (ref "R49") (pin "2") (pintype "passive"))
      (node (ref "R50") (pin "1") (pintype "passive"))
      (node (ref "R52") (pin "2") (pintype "passive"))
      (node (ref "R60") (pin "2") (pintype "passive"))
      (node (ref "R61") (pin "1") (pintype "passive"))
      (node (ref "SW3") (pin "1") (pinfunction "A1_1") (pintype "passive"))
      (node (ref "U10") (pin "19") (pinfunction "19_19") (pintype "passive"))
      (node (ref "U10") (pin "20") (pinfunction "20_20") (pintype "passive"))
      (node (ref "U13") (pin "2") (pinfunction "2_2") (pintype "passive"))
      (node (ref "U2") (pin "3") (pinfunction "GND_3") (pintype "passive"))
      (node (ref "U4") (pin "3") (pinfunction "GND_3") (pintype "passive"))
      (node (ref "U5") (pin "2") (pinfunction "GND_2") (pintype "passive"))
      (node (ref "U6") (pin "8") (pinfunction "GND_8") (pintype "passive"))
      (node (ref "XA1") (pin "GND1") (pinfunction "GND_GND1") (pintype "passive"))
      (node (ref "XA1") (pin "GND2") (pinfunction "GND_GND2") (pintype "passive"))
      (node (ref "XA1") (pin "GND3") (pinfunction "GND_GND3") (pintype "passive"))
      (node (ref "XA1") (pin "GND5") (pinfunction "GND_GND5") (pintype "passive"))
      (node (ref "XA1") (pin "GND6") (pinfunction "GND_GND6") (pintype "passive"))
    )
    (net (code "75") (name "Net-(AAAAD5-K)") (class "Default")
      (node (ref "AAAAD5") (pin "1") (pinfunction "K_1") (pintype "passive"))
      (node (ref "AAAAL2") (pin "1") (pinfunction "1_1") (pintype "passive"))
      (node (ref "AAAAU8") (pin "2") (pinfunction "Output_2") (pintype "passive"))
    )
    (net (code "76") (name "Net-(AAAALED8-A)") (class "Default")
      (node (ref "AAAALED8") (pin "1") (pinfunction "A_1") (pintype "passive"))
      (node (ref "AAAAR13") (pin "1") (pinfunction "1_1") (pintype "passive"))
    )
    (net (code "77") (name "Net-(AAAAR14-Pad2)") (class "Default")
      (node (ref "AAAAR14") (pin "2") (pinfunction "2_2") (pintype "passive"))
      (node (ref "AAAAU1") (pin "1") (pinfunction "1_1") (pintype "passive"))
    )
    (net (code "78") (name "Net-(AAAAU8-Feedback)") (class "Default")
      (node (ref "AAAAU1") (pin "2") (pinfunction "2_2") (pintype "passive"))
      (node (ref "AAAAU8") (pin "4") (pinfunction "Feedback_4") (pintype "passive"))
    )
    (net (code "79") (name "Net-(C4-Pad1)") (class "Default")
      (node (ref "C4") (pin "1") (pintype "passive"))
      (node (ref "R29") (pin "2") (pintype "passive"))
      (node (ref "R30") (pin "1") (pintype "passive"))
      (node (ref "R32") (pin "2") (pintype "passive"))
    )
    (net (code "80") (name "Net-(D2-A)") (class "Default")
      (node (ref "D2") (pin "2") (pinfunction "A_2") (pintype "passive"))
      (node (ref "R12") (pin "2") (pintype "passive"))
    )
    (net (code "81") (name "Net-(D3-A)") (class "Default")
      (node (ref "D3") (pin "2") (pinfunction "A_2") (pintype "passive"))
      (node (ref "R9") (pin "1") (pintype "passive"))
    )
    (net (code "82") (name "Net-(D3-K)") (class "Default")
      (node (ref "D3") (pin "1") (pinfunction "K_1") (pintype "passive"))
      (node (ref "D5") (pin "2") (pinfunction "A_2") (pintype "passive"))
    )
    (net (code "83") (name "Net-(D4-A)") (class "Default")
      (node (ref "D4") (pin "2") (pinfunction "A_2") (pintype "passive"))
      (node (ref "R10") (pin "1") (pintype "passive"))
    )
    (net (code "84") (name "Net-(D4-K)") (class "Default")
      (node (ref "D4") (pin "1") (pinfunction "K_1") (pintype "passive"))
      (node (ref "D6") (pin "2") (pinfunction "A_2") (pintype "passive"))
    )
    (net (code "85") (name "Net-(D7-A)") (class "Default")
      (node (ref "D7") (pin "2") (pinfunction "A_2") (pintype "passive"))
      (node (ref "R23") (pin "1") (pintype "passive"))
    )
    (net (code "86") (name "Net-(D8-A)") (class "Default")
      (node (ref "D8") (pin "2") (pinfunction "A_2") (pintype "passive"))
      (node (ref "R24") (pin "1") (pintype "passive"))
    )
    (net (code "87") (name "Net-(D9-A)") (class "Default")
      (node (ref "D9") (pin "2") (pinfunction "A_2") (pintype "passive"))
      (node (ref "R25") (pin "2") (pintype "passive"))
    )
    (net (code "88") (name "Net-(D10-A)") (class "Default")
      (node (ref "D10") (pin "2") (pinfunction "A_2") (pintype "passive"))
      (node (ref "R26") (pin "2") (pintype "passive"))
    )
    (net (code "89") (name "Net-(D11-A)") (class "Default")
      (node (ref "D11") (pin "2") (pinfunction "A_2") (pintype "passive"))
      (node (ref "D7") (pin "1") (pinfunction "K_1") (pintype "passive"))
    )
    (net (code "90") (name "Net-(D12-A)") (class "Default")
      (node (ref "D12") (pin "2") (pinfunction "A_2") (pintype "passive"))
      (node (ref "D8") (pin "1") (pinfunction "K_1") (pintype "passive"))
    )
    (net (code "91") (name "Net-(IC3-Pin_2)") (class "Default")
      (node (ref "IC3") (pin "2") (pinfunction "Pin_2_2") (pintype "passive"))
      (node (ref "JP2") (pin "1") (pinfunction "A_1") (pintype "passive"))
    )
    (net (code "92") (name "Net-(IC3-Pin_3)") (class "Default")
      (node (ref "IC3") (pin "3") (pinfunction "Pin_3_3") (pintype "passive"))
      (node (ref "JP3") (pin "1") (pinfunction "A_1") (pintype "passive"))
    )
    (net (code "93") (name "Net-(J1-Pin_1)") (class "Default")
      (node (ref "F1") (pin "2") (pintype "passive"))
      (node (ref "J1") (pin "1") (pinfunction "Pin_1_1") (pintype "passive"))
      (node (ref "J1") (pin "2") (pinfunction "Pin_2_2") (pintype "passive"))
      (node (ref "J1") (pin "3") (pinfunction "Pin_3_3") (pintype "passive"))
      (node (ref "J1") (pin "4") (pinfunction "Pin_4_4") (pintype "passive"))
      (node (ref "J1") (pin "5") (pinfunction "Pin_5_5") (pintype "passive"))
    )
    (net (code "94") (name "Net-(J2-Pin_5)") (class "Default")
      (node (ref "J2") (pin "5") (pinfunction "Pin_5_5") (pintype "passive"))
      (node (ref "R52") (pin "1") (pintype "passive"))
      (node (ref "R53") (pin "2") (pintype "passive"))
    )
    (net (code "95") (name "Net-(J5-Pin_1)") (class "Default")
      (node (ref "J5") (pin "1") (pinfunction "Pin_1_1") (pintype "passive"))
      (node (ref "R63") (pin "2") (pintype "passive"))
    )
    (net (code "96") (name "Net-(J5-Pin_2)") (class "Default")
      (node (ref "J5") (pin "2") (pinfunction "Pin_2_2") (pintype "passive"))
      (node (ref "R62") (pin "1") (pintype "passive"))
    )
    (net (code "97") (name "Net-(JP2-B)") (class "Default")
      (node (ref "JP2") (pin "3") (pinfunction "B_3") (pintype "passive"))
      (node (ref "R43") (pin "2") (pintype "passive"))
    )
    (net (code "98") (name "Net-(JP3-B)") (class "Default")
      (node (ref "JP3") (pin "3") (pinfunction "B_3") (pintype "passive"))
      (node (ref "R44") (pin "2") (pintype "passive"))
    )
    (net (code "99") (name "Net-(JP4-B)") (class "Default")
      (node (ref "JP4") (pin "2") (pinfunction "B_2") (pintype "passive"))
      (node (ref "R41") (pin "1") (pintype "passive"))
    )
    (net (code "100") (name "Net-(JP5-B)") (class "Default")
      (node (ref "JP5") (pin "2") (pinfunction "B_2") (pintype "passive"))
      (node (ref "R42") (pin "1") (pintype "passive"))
    )
    (net (code "101") (name "Net-(JP11-B)") (class "Default")
      (node (ref "JP11") (pin "3") (pinfunction "B_3") (pintype "passive"))
      (node (ref "R55") (pin "2") (pintype "passive"))
    )
    (net (code "102") (name "Net-(JP11-C)") (class "Default")
      (node (ref "JP11") (pin "2") (pinfunction "C_2") (pintype "passive"))
      (node (ref "U5") (pin "1") (pinfunction "VOUT_1") (pintype "passive"))
    )
    (net (code "103") (name "Net-(Q4-G)") (class "Default")
      (node (ref "Q4") (pin "1") (pinfunction "G_1") (pintype "passive"))
      (node (ref "R5") (pin "1") (pintype "passive"))
    )
    (net (code "104") (name "Net-(Q5-G)") (class "Default")
      (node (ref "Q5") (pin "1") (pinfunction "G_1") (pintype "passive"))
      (node (ref "R6") (pin "1") (pintype "passive"))
    )
    (net (code "105") (name "Net-(Q6-G)") (class "Default")
      (node (ref "Q6") (pin "1") (pinfunction "G_1") (pintype "passive"))
      (node (ref "R18") (pin "1") (pintype "passive"))
    )
    (net (code "106") (name "Net-(Q7-G)") (class "Default")
      (node (ref "Q7") (pin "1") (pinfunction "G_1") (pintype "passive"))
      (node (ref "R17") (pin "1") (pintype "passive"))
    )
    (net (code "107") (name "Net-(Q8-G)") (class "Default")
      (node (ref "Q8") (pin "1") (pinfunction "G_1") (pintype "passive"))
      (node (ref "R57") (pin "1") (pintype "passive"))
    )
    (net (code "108") (name "Net-(Q9-G)") (class "Default")
      (node (ref "Q9") (pin "1") (pinfunction "G_1") (pintype "passive"))
      (node (ref "R56") (pin "1") (pintype "passive"))
    )
    (net (code "109") (name "Net-(Q10-G)") (class "Default")
      (node (ref "Q10") (pin "1") (pinfunction "G_1") (pintype "passive"))
      (node (ref "R47") (pin "1") (pintype "passive"))
    )
    (net (code "110") (name "Net-(Q11-G)") (class "Default")
      (node (ref "Q11") (pin "1") (pinfunction "G_1") (pintype "passive"))
      (node (ref "R48") (pin "1") (pintype "passive"))
    )
    (net (code "111") (name "Net-(SW3-B1)") (class "Default")
      (node (ref "C17") (pin "2") (pintype "passive"))
      (node (ref "R46") (pin "2") (pintype "passive"))
      (node (ref "SW3") (pin "2") (pinfunction "B1_2") (pintype "passive"))
    )
    (net (code "112") (name "Net-(U2-IN_A)") (class "Default")
      (node (ref "R7") (pin "1") (pintype "passive"))
      (node (ref "U2") (pin "2") (pinfunction "IN_A_2") (pintype "passive"))
    )
    (net (code "113") (name "Net-(U2-IN_B)") (class "Default")
      (node (ref "R8") (pin "1") (pintype "passive"))
      (node (ref "U2") (pin "4") (pinfunction "IN_B_4") (pintype "passive"))
    )
    (net (code "114") (name "Net-(U2-OUT_A)") (class "Default")
      (node (ref "R11") (pin "1") (pintype "passive"))
      (node (ref "R13") (pin "2") (pintype "passive"))
      (node (ref "U2") (pin "7") (pinfunction "OUT_A_7") (pintype "passive"))
    )
    (net (code "115") (name "Net-(U2-OUT_B)") (class "Default")
      (node (ref "R12") (pin "1") (pintype "passive"))
      (node (ref "R14") (pin "2") (pintype "passive"))
      (node (ref "U2") (pin "5") (pinfunction "OUT_B_5") (pintype "passive"))
    )
    (net (code "116") (name "Net-(U4-IN_A)") (class "Default")
      (node (ref "R21") (pin "1") (pintype "passive"))
      (node (ref "U4") (pin "2") (pinfunction "IN_A_2") (pintype "passive"))
    )
    (net (code "117") (name "Net-(U4-IN_B)") (class "Default")
      (node (ref "R22") (pin "1") (pintype "passive"))
      (node (ref "U4") (pin "4") (pinfunction "IN_B_4") (pintype "passive"))
    )
    (net (code "118") (name "Net-(U4-OUT_A)") (class "Default")
      (node (ref "R25") (pin "1") (pintype "passive"))
      (node (ref "R27") (pin "2") (pintype "passive"))
      (node (ref "U4") (pin "7") (pinfunction "OUT_A_7") (pintype "passive"))
    )
    (net (code "119") (name "Net-(U4-OUT_B)") (class "Default")
      (node (ref "R26") (pin "1") (pintype "passive"))
      (node (ref "R28") (pin "2") (pintype "passive"))
      (node (ref "U4") (pin "5") (pinfunction "OUT_B_5") (pintype "passive"))
    )
    (net (code "120") (name "Net-(U10-Pad3)") (class "Default")
      (node (ref "U10") (pin "3") (pinfunction "3_3") (pintype "passive"))
      (node (ref "U7") (pin "1") (pinfunction "1_1") (pintype "passive"))
    )
    (net (code "121") (name "Net-(U10-Pad4)") (class "Default")
      (node (ref "U10") (pin "4") (pinfunction "4_4") (pintype "passive"))
      (node (ref "U8") (pin "8") (pinfunction "8_8") (pintype "passive"))
    )
    (net (code "122") (name "Net-(U10-Pad5)") (class "Default")
      (node (ref "U10") (pin "5") (pinfunction "5_5") (pintype "passive"))
      (node (ref "U7") (pin "2") (pinfunction "2_2") (pintype "passive"))
    )
    (net (code "123") (name "Net-(U10-Pad6)") (class "Default")
      (node (ref "U10") (pin "6") (pinfunction "6_6") (pintype "passive"))
      (node (ref "U8") (pin "7") (pinfunction "7_7") (pintype "passive"))
    )
    (net (code "124") (name "Net-(U10-Pad7)") (class "Default")
      (node (ref "U10") (pin "7") (pinfunction "7_7") (pintype "passive"))
      (node (ref "U7") (pin "3") (pinfunction "3_3") (pintype "passive"))
    )
    (net (code "125") (name "Net-(U10-Pad8)") (class "Default")
      (node (ref "U10") (pin "8") (pinfunction "8_8") (pintype "passive"))
      (node (ref "U8") (pin "6") (pinfunction "6_6") (pintype "passive"))
    )
    (net (code "126") (name "Net-(U10-Pad9)") (class "Default")
      (node (ref "U10") (pin "9") (pinfunction "9_9") (pintype "passive"))
      (node (ref "U7") (pin "4") (pinfunction "4_4") (pintype "passive"))
    )
    (net (code "127") (name "Net-(U10-Pad10)") (class "Default")
      (node (ref "U10") (pin "10") (pinfunction "10_10") (pintype "passive"))
      (node (ref "U8") (pin "5") (pinfunction "5_5") (pintype "passive"))
    )
    (net (code "128") (name "Net-(U10-Pad11)") (class "Default")
      (node (ref "U10") (pin "11") (pinfunction "11_11") (pintype "passive"))
      (node (ref "U7") (pin "5") (pinfunction "5_5") (pintype "passive"))
    )
    (net (code "129") (name "Net-(U10-Pad12)") (class "Default")
      (node (ref "U10") (pin "12") (pinfunction "12_12") (pintype "passive"))
      (node (ref "U8") (pin "4") (pinfunction "4_4") (pintype "passive"))
    )
    (net (code "130") (name "Net-(U10-Pad13)") (class "Default")
      (node (ref "U10") (pin "13") (pinfunction "13_13") (pintype "passive"))
      (node (ref "U7") (pin "6") (pinfunction "6_6") (pintype "passive"))
    )
    (net (code "131") (name "Net-(U10-Pad14)") (class "Default")
      (node (ref "U10") (pin "14") (pinfunction "14_14") (pintype "passive"))
      (node (ref "U8") (pin "3") (pinfunction "3_3") (pintype "passive"))
    )
    (net (code "132") (name "Net-(U10-Pad15)") (class "Default")
      (node (ref "U10") (pin "15") (pinfunction "15_15") (pintype "passive"))
      (node (ref "U7") (pin "7") (pinfunction "7_7") (pintype "passive"))
    )
    (net (code "133") (name "Net-(U10-Pad16)") (class "Default")
      (node (ref "U10") (pin "16") (pinfunction "16_16") (pintype "passive"))
      (node (ref "U8") (pin "2") (pinfunction "2_2") (pintype "passive"))
    )
    (net (code "134") (name "Net-(U10-Pad17)") (class "Default")
      (node (ref "U10") (pin "17") (pinfunction "17_17") (pintype "passive"))
      (node (ref "U7") (pin "8") (pinfunction "8_8") (pintype "passive"))
    )
    (net (code "135") (name "Net-(U10-Pad18)") (class "Default")
      (node (ref "U10") (pin "18") (pinfunction "18_18") (pintype "passive"))
      (node (ref "U8") (pin "1") (pinfunction "1_1") (pintype "passive"))
    )
    (net (code "136") (name "VDD") (class "Default")
      (node (ref "A1") (pin "13") (pinfunction "RST_13") (pintype "passive"))
      (node (ref "A1") (pin "14") (pinfunction "SLP_14") (pintype "passive"))
      (node (ref "AAAA1") (pin "OUT+") (pinfunction "OUT+_OUT+") (pintype "passive"))
      (node (ref "AAAAC3") (pin "1") (pinfunction "1_1") (pintype "passive"))
      (node (ref "AAAAC5") (pin "2") (pinfunction "2_2") (pintype "passive"))
      (node (ref "AAAAL2") (pin "2") (pinfunction "2_2") (pintype "passive"))
      (node (ref "AAAAR13") (pin "2") (pinfunction "2_2") (pintype "passive"))
      (node (ref "AAAAU1") (pin "3") (pinfunction "3_3") (pintype "passive"))
      (node (ref "C1") (pin "2") (pintype "passive"))
      (node (ref "C2") (pin "2") (pintype "passive"))
      (node (ref "F1") (pin "1") (pintype "passive"))
      (node (ref "F2") (pin "1") (pintype "passive"))
      (node (ref "IC3") (pin "5") (pinfunction "Pin_5_5") (pintype "passive"))
      (node (ref "J2") (pin "2") (pinfunction "Pin_2_2") (pintype "passive"))
      (node (ref "JP1") (pin "1") (pinfunction "A_1") (pintype "passive"))
      (node (ref "R54") (pin "2") (pintype "passive"))
      (node (ref "R59") (pin "1") (pinfunction "1_1") (pintype "passive"))
      (node (ref "U5") (pin "3") (pinfunction "VCC_3") (pintype "passive"))
      (node (ref "XA1") (pin "5V1") (pinfunction "5V_5V1") (pintype "passive"))
      (node (ref "XA1") (pin "5V3") (pinfunction "5V_5V3") (pintype "passive"))
      (node (ref "XA1") (pin "5V4") (pinfunction "5V_5V4") (pintype "passive"))
    )
    (net (code "137") (name "VDDA") (class "Default")
      (node (ref "F2") (pin "2") (pintype "passive"))
      (node (ref "J4") (pin "25") (pinfunction "Pin_25_25") (pintype "passive"))
      (node (ref "J4") (pin "26") (pinfunction "Pin_26_26") (pintype "passive"))
      (node (ref "R33") (pin "1") (pintype "passive"))
      (node (ref "R35") (pin "2") (pintype "passive"))
      (node (ref "R36") (pin "2") (pintype "passive"))
      (node (ref "R41") (pin "2") (pintype "passive"))
      (node (ref "R42") (pin "2") (pintype "passive"))
      (node (ref "U10") (pin "1") (pinfunction "1_1") (pintype "passive"))
      (node (ref "U10") (pin "2") (pinfunction "2_2") (pintype "passive"))
      (node (ref "U6") (pin "16") (pinfunction "V+_16") (pintype "passive"))
    )
    (net (code "138") (name "Vdrive") (class "Default")
      (node (ref "C24") (pin "2") (pintype "passive"))
      (node (ref "C25") (pin "2") (pintype "passive"))
      (node (ref "C26") (pin "2") (pintype "passive"))
      (node (ref "C27") (pin "2") (pintype "passive"))
      (node (ref "JP1") (pin "2") (pinfunction "C_2") (pintype "passive"))
      (node (ref "U2") (pin "6") (pinfunction "VDD_6") (pintype "passive"))
      (node (ref "U4") (pin "6") (pinfunction "VDD_6") (pintype "passive"))
    )
    (net (code "139") (name "unconnected-(A1-FLT-Pad2)") (class "Default")
      (node (ref "A1") (pin "2") (pinfunction "FLT_2") (pintype "passive+no_connect"))
    )
    (net (code "140") (name "unconnected-(A1-M0-Pad10)") (class "Default")
      (node (ref "A1") (pin "10") (pinfunction "M0_10") (pintype "passive+no_connect"))
    )
    (net (code "141") (name "unconnected-(A1-M1-Pad11)") (class "Default")
      (node (ref "A1") (pin "11") (pinfunction "M1_11") (pintype "passive+no_connect"))
    )
    (net (code "142") (name "unconnected-(A1-M2-Pad12)") (class "Default")
      (node (ref "A1") (pin "12") (pinfunction "M2_12") (pintype "passive+no_connect"))
    )
    (net (code "143") (name "unconnected-(J2-Pin_6-Pad6)") (class "Default")
      (node (ref "J2") (pin "6") (pinfunction "Pin_6_6") (pintype "passive+no_connect"))
    )
    (net (code "144") (name "unconnected-(R11-Pad2)") (class "Default")
      (node (ref "R11") (pin "2") (pintype "passive"))
    )
    (net (code "145") (name "unconnected-(U2-NC-Pad1)") (class "Default")
      (node (ref "U2") (pin "1") (pinfunction "NC_1") (pintype "passive+no_connect"))
    )
    (net (code "146") (name "unconnected-(U2-NC-Pad8)") (class "Default")
      (node (ref "U2") (pin "8") (pinfunction "NC_8") (pintype "passive+no_connect"))
    )
    (net (code "147") (name "unconnected-(U4-NC-Pad1)") (class "Default")
      (node (ref "U4") (pin "1") (pinfunction "NC_1") (pintype "passive+no_connect"))
    )
    (net (code "148") (name "unconnected-(U4-NC-Pad8)") (class "Default")
      (node (ref "U4") (pin "8") (pinfunction "NC_8") (pintype "passive+no_connect"))
    )
    (net (code "149") (name "unconnected-(U6-I7-Pad7)") (class "Default")
      (node (ref "U6") (pin "7") (pinfunction "I7_7") (pintype "passive+no_connect"))
    )
    (net (code "150") (name "unconnected-(U6-I11-Pad12)") (class "Default")
      (node (ref "U6") (pin "12") (pinfunction "I11_12") (pintype "passive+no_connect"))
    )
    (net (code "151") (name "unconnected-(U6-I12-Pad13)") (class "Default")
      (node (ref "U6") (pin "13") (pinfunction "I12_13") (pintype "passive+no_connect"))
    )
    (net (code "152") (name "unconnected-(U6-I14-Pad15)") (class "Default")
      (node (ref "U6") (pin "15") (pinfunction "I14_15") (pintype "passive+no_connect"))
    )
    (net (code "153") (name "unconnected-(XA1-3.3V-Pad3V3)") (class "Default")
      (node (ref "XA1") (pin "3V3") (pinfunction "3.3V_3V3") (pintype "passive+no_connect"))
    )
    (net (code "154") (name "unconnected-(XA1-D14_TX3-PadD14)") (class "Default")
      (node (ref "XA1") (pin "D14") (pinfunction "D14_TX3_D14") (pintype "passive+no_connect"))
    )
    (net (code "155") (name "unconnected-(XA1-D15_RX3-PadD15)") (class "Default")
      (node (ref "XA1") (pin "D15") (pinfunction "D15_RX3_D15") (pintype "passive+no_connect"))
    )
    (net (code "156") (name "unconnected-(XA1-D53_SS-PadD53)") (class "Default")
      (node (ref "XA1") (pin "D53") (pinfunction "D53_SS_D53") (pintype "passive+no_connect"))
    )
    (net (code "157") (name "unconnected-(XA1-IOREF-PadIORF)") (class "Default")
      (node (ref "XA1") (pin "IORF") (pinfunction "IOREF_IORF") (pintype "passive+no_connect"))
    )
    (net (code "158") (name "unconnected-(XA1-PadA6)") (class "Default")
      (node (ref "XA1") (pin "A6") (pinfunction "A6_A6") (pintype "passive+no_connect"))
    )
    (net (code "159") (name "unconnected-(XA1-PadA7)") (class "Default")
      (node (ref "XA1") (pin "A7") (pinfunction "A7_A7") (pintype "passive+no_connect"))
    )
    (net (code "160") (name "unconnected-(XA1-PadA11)") (class "Default")
      (node (ref "XA1") (pin "A11") (pinfunction "A11_A11") (pintype "passive+no_connect"))
    )
    (net (code "161") (name "unconnected-(XA1-PadA12)") (class "Default")
      (node (ref "XA1") (pin "A12") (pinfunction "A12_A12") (pintype "passive+no_connect"))
    )
    (net (code "162") (name "unconnected-(XA1-PadA13)") (class "Default")
      (node (ref "XA1") (pin "A13") (pinfunction "A13_A13") (pintype "passive+no_connect"))
    )
    (net (code "163") (name "unconnected-(XA1-PadA14)") (class "Default")
      (node (ref "XA1") (pin "A14") (pinfunction "A14_A14") (pintype "passive+no_connect"))
    )
    (net (code "164") (name "unconnected-(XA1-PadA15)") (class "Default")
      (node (ref "XA1") (pin "A15") (pinfunction "A15_A15") (pintype "passive+no_connect"))
    )
    (net (code "165") (name "unconnected-(XA1-PadAREF)") (class "Default")
      (node (ref "XA1") (pin "AREF") (pinfunction "AREF_AREF") (pintype "passive+no_connect"))
    )
    (net (code "166") (name "unconnected-(XA1-PadD12)") (class "Default")
      (node (ref "XA1") (pin "D12") (pinfunction "D12_D12") (pintype "passive+no_connect"))
    )
    (net (code "167") (name "unconnected-(XA1-PadD13)") (class "Default")
      (node (ref "XA1") (pin "D13") (pinfunction "D13_D13") (pintype "passive+no_connect"))
    )
    (net (code "168") (name "unconnected-(XA1-PadD22)") (class "Default")
      (node (ref "XA1") (pin "D22") (pinfunction "D22_D22") (pintype "passive+no_connect"))
    )
    (net (code "169") (name "unconnected-(XA1-PadD23)") (class "Default")
      (node (ref "XA1") (pin "D23") (pinfunction "D23_D23") (pintype "passive+no_connect"))
    )
    (net (code "170") (name "unconnected-(XA1-PadD25)") (class "Default")
      (node (ref "XA1") (pin "D25") (pinfunction "D25_D25") (pintype "passive+no_connect"))
    )
    (net (code "171") (name "unconnected-(XA1-PadD26)") (class "Default")
      (node (ref "XA1") (pin "D26") (pinfunction "D26_D26") (pintype "passive+no_connect"))
    )
    (net (code "172") (name "unconnected-(XA1-PadD27)") (class "Default")
      (node (ref "XA1") (pin "D27") (pinfunction "D27_D27") (pintype "passive+no_connect"))
    )
    (net (code "173") (name "unconnected-(XA1-PadD28)") (class "Default")
      (node (ref "XA1") (pin "D28") (pinfunction "D28_D28") (pintype "passive+no_connect"))
    )
    (net (code "174") (name "unconnected-(XA1-PadD29)") (class "Default")
      (node (ref "XA1") (pin "D29") (pinfunction "D29_D29") (pintype "passive+no_connect"))
    )
    (net (code "175") (name "unconnected-(XA1-PadD30)") (class "Default")
      (node (ref "XA1") (pin "D30") (pinfunction "D30_D30") (pintype "passive+no_connect"))
    )
    (net (code "176") (name "unconnected-(XA1-PadD31)") (class "Default")
      (node (ref "XA1") (pin "D31") (pinfunction "D31_D31") (pintype "passive+no_connect"))
    )
    (net (code "177") (name "unconnected-(XA1-PadD32)") (class "Default")
      (node (ref "XA1") (pin "D32") (pinfunction "D32_D32") (pintype "passive+no_connect"))
    )
    (net (code "178") (name "unconnected-(XA1-PadD33)") (class "Default")
      (node (ref "XA1") (pin "D33") (pinfunction "D33_D33") (pintype "passive+no_connect"))
    )
    (net (code "179") (name "unconnected-(XA1-PadD34)") (class "Default")
      (node (ref "XA1") (pin "D34") (pinfunction "D34_D34") (pintype "passive+no_connect"))
    )
    (net (code "180") (name "unconnected-(XA1-PadD35)") (class "Default")
      (node (ref "XA1") (pin "D35") (pinfunction "D35_D35") (pintype "passive+no_connect"))
    )
    (net (code "181") (name "unconnected-(XA1-PadD36)") (class "Default")
      (node (ref "XA1") (pin "D36") (pinfunction "D36_D36") (pintype "passive+no_connect"))
    )
    (net (code "182") (name "unconnected-(XA1-PadD37)") (class "Default")
      (node (ref "XA1") (pin "D37") (pinfunction "D37_D37") (pintype "passive+no_connect"))
    )
    (net (code "183") (name "unconnected-(XA1-PadD39)") (class "Default")
      (node (ref "XA1") (pin "D39") (pinfunction "D39_D39") (pintype "passive+no_connect"))
    )
    (net (code "184") (name "unconnected-(XA1-PadD41)") (class "Default")
      (node (ref "XA1") (pin "D41") (pinfunction "D41_D41") (pintype "passive+no_connect"))
    )
    (net (code "185") (name "unconnected-(XA1-PadD42)") (class "Default")
      (node (ref "XA1") (pin "D42") (pinfunction "D42_D42") (pintype "passive+no_connect"))
    )
    (net (code "186") (name "unconnected-(XA1-PadD43)") (class "Default")
      (node (ref "XA1") (pin "D43") (pinfunction "D43_D43") (pintype "passive+no_connect"))
    )
    (net (code "187") (name "unconnected-(XA1-PadD44)") (class "Default")
      (node (ref "XA1") (pin "D44") (pinfunction "D44_D44") (pintype "passive+no_connect"))
    )
    (net (code "188") (name "unconnected-(XA1-PadD46)") (class "Default")
      (node (ref "XA1") (pin "D46") (pinfunction "D46_D46") (pintype "passive+no_connect"))
    )
    (net (code "189") (name "unconnected-(XA1-PadD48)") (class "Default")
      (node (ref "XA1") (pin "D48") (pinfunction "D48_D48") (pintype "passive+no_connect"))
    )
    (net (code "190") (name "unconnected-(XA1-PadSCL)") (class "Default")
      (node (ref "XA1") (pin "SCL") (pinfunction "SCL_SCL") (pintype "passive+no_connect"))
    )
    (net (code "191") (name "unconnected-(XA1-PadSDA)") (class "Default")
      (node (ref "XA1") (pin "SDA") (pinfunction "SDA_SDA") (pintype "passive+no_connect"))
    )
    (net (code "192") (name "unconnected-(XA1-PadVIN)") (class "Default")
      (node (ref "XA1") (pin "VIN") (pinfunction "VIN_VIN") (pintype "passive+no_connect"))
    )
    (net (code "193") (name "unconnected-(XA1-SPI_5V-Pad5V2)") (class "Default")
      (node (ref "XA1") (pin "5V2") (pinfunction "SPI_5V_5V2") (pintype "passive+no_connect"))
    )
    (net (code "194") (name "unconnected-(XA1-SPI_GND-PadGND4)") (class "Default")
      (node (ref "XA1") (pin "GND4") (pinfunction "SPI_GND_GND4") (pintype "passive+no_connect"))
    )
    (net (code "195") (name "unconnected-(XA1-SPI_MISO-PadMISO)") (class "Default")
      (node (ref "XA1") (pin "MISO") (pinfunction "SPI_MISO_MISO") (pintype "passive+no_connect"))
    )
    (net (code "196") (name "unconnected-(XA1-SPI_MOSI-PadMOSI)") (class "Default")
      (node (ref "XA1") (pin "MOSI") (pinfunction "SPI_MOSI_MOSI") (pintype "passive+no_connect"))
    )
    (net (code "197") (name "unconnected-(XA1-SPI_RESET-PadRST2)") (class "Default")
      (node (ref "XA1") (pin "RST2") (pinfunction "SPI_RESET_RST2") (pintype "passive+no_connect"))
    )
    (net (code "198") (name "unconnected-(XA1-SPI_SCK-PadSCK)") (class "Default")
      (node (ref "XA1") (pin "SCK") (pinfunction "SPI_SCK_SCK") (pintype "passive+no_connect"))
    )
  )
)
